# FPGA-Validation.net
KiCad netlist of a schematic drawn in EAGLE
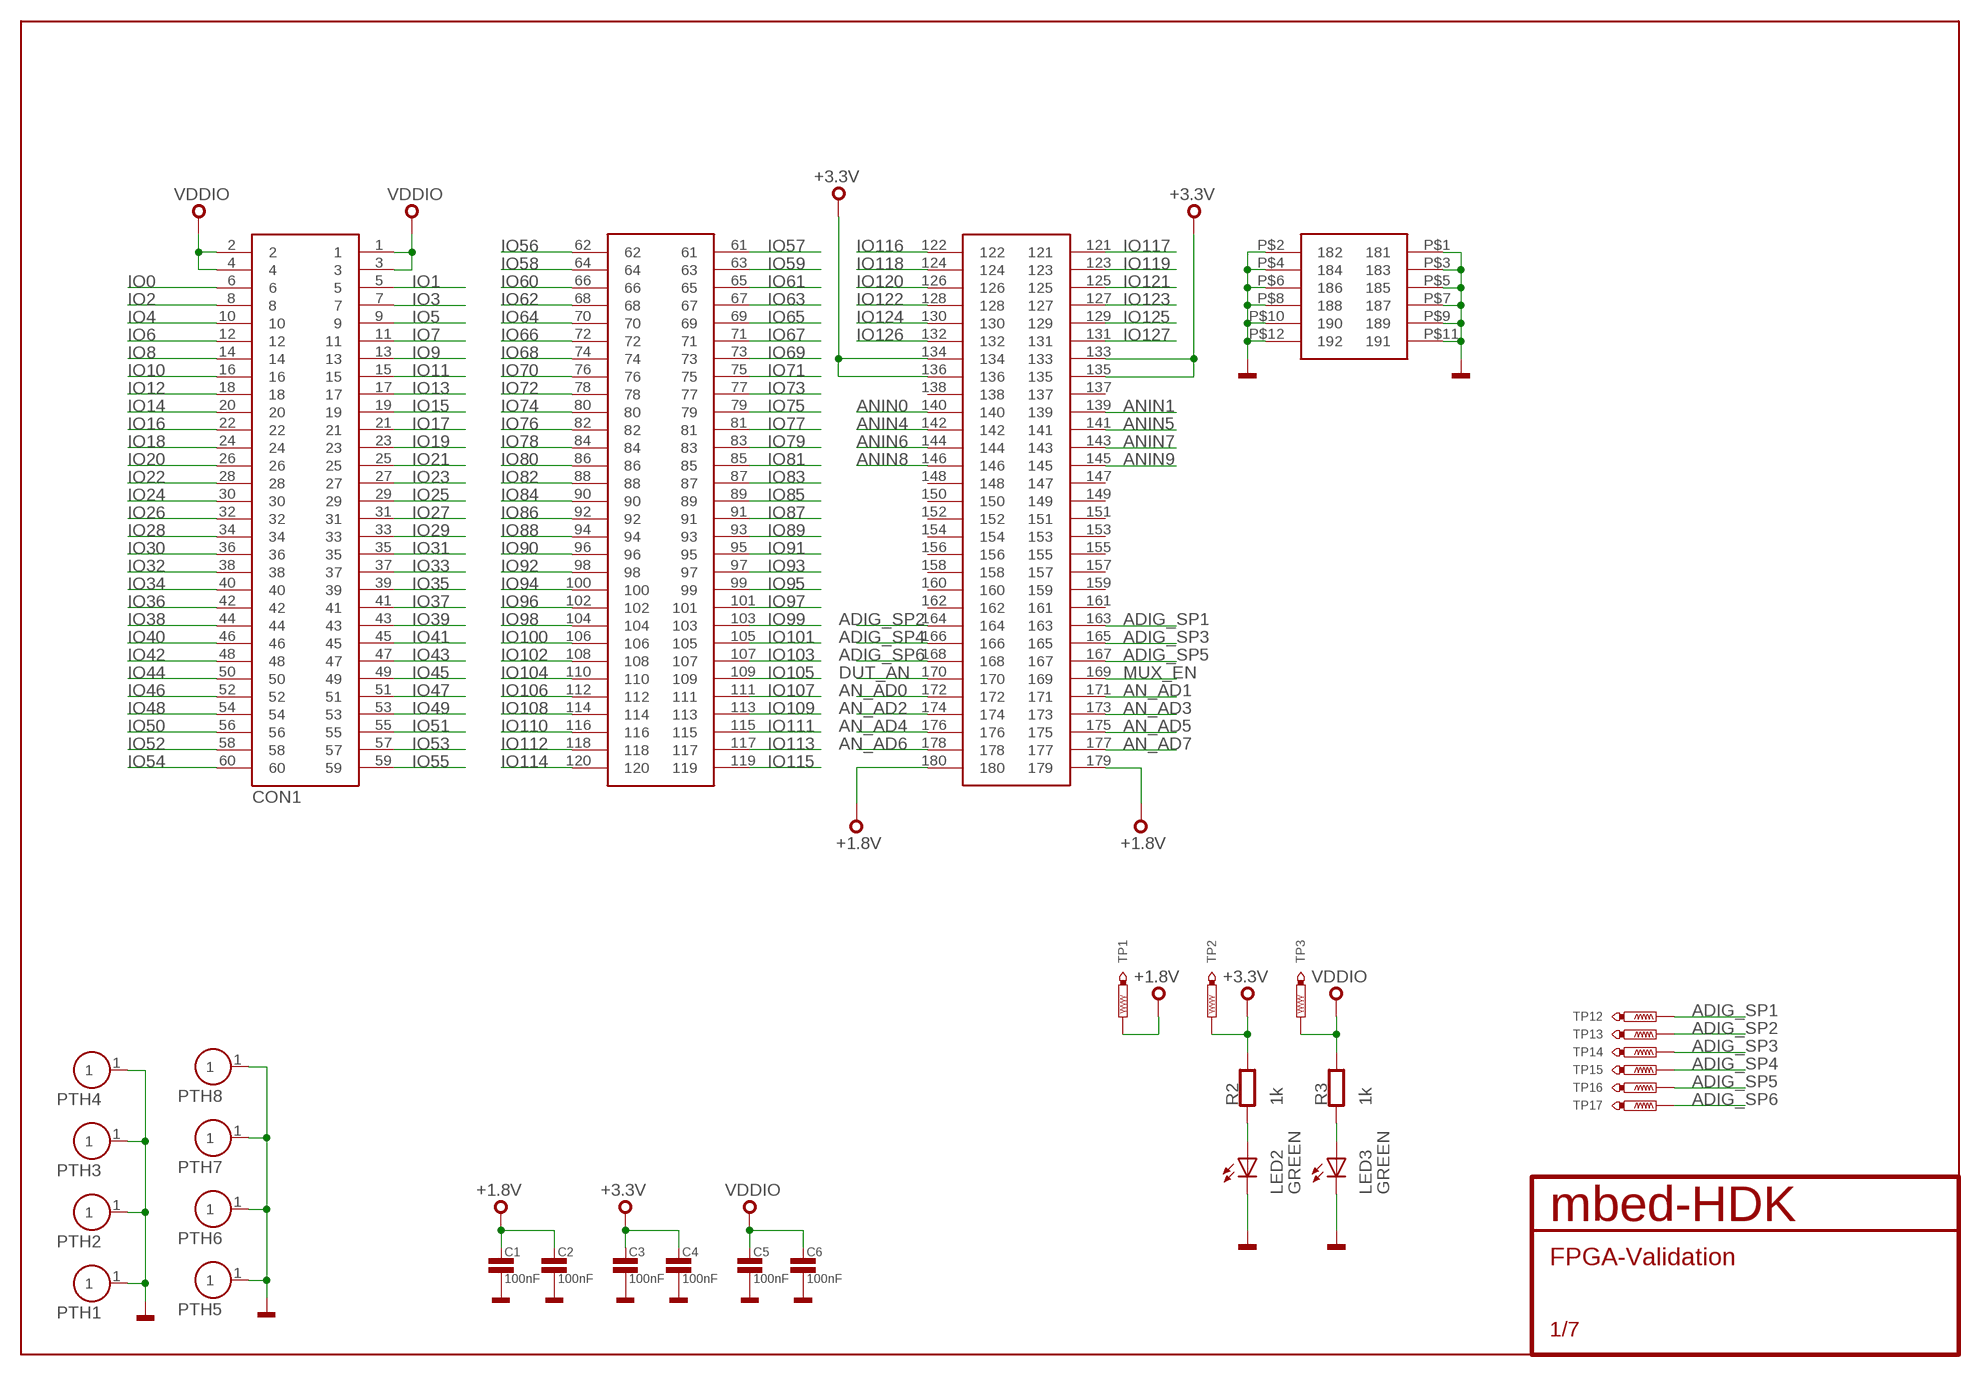
[diagram p0: schematic, sheet 1]
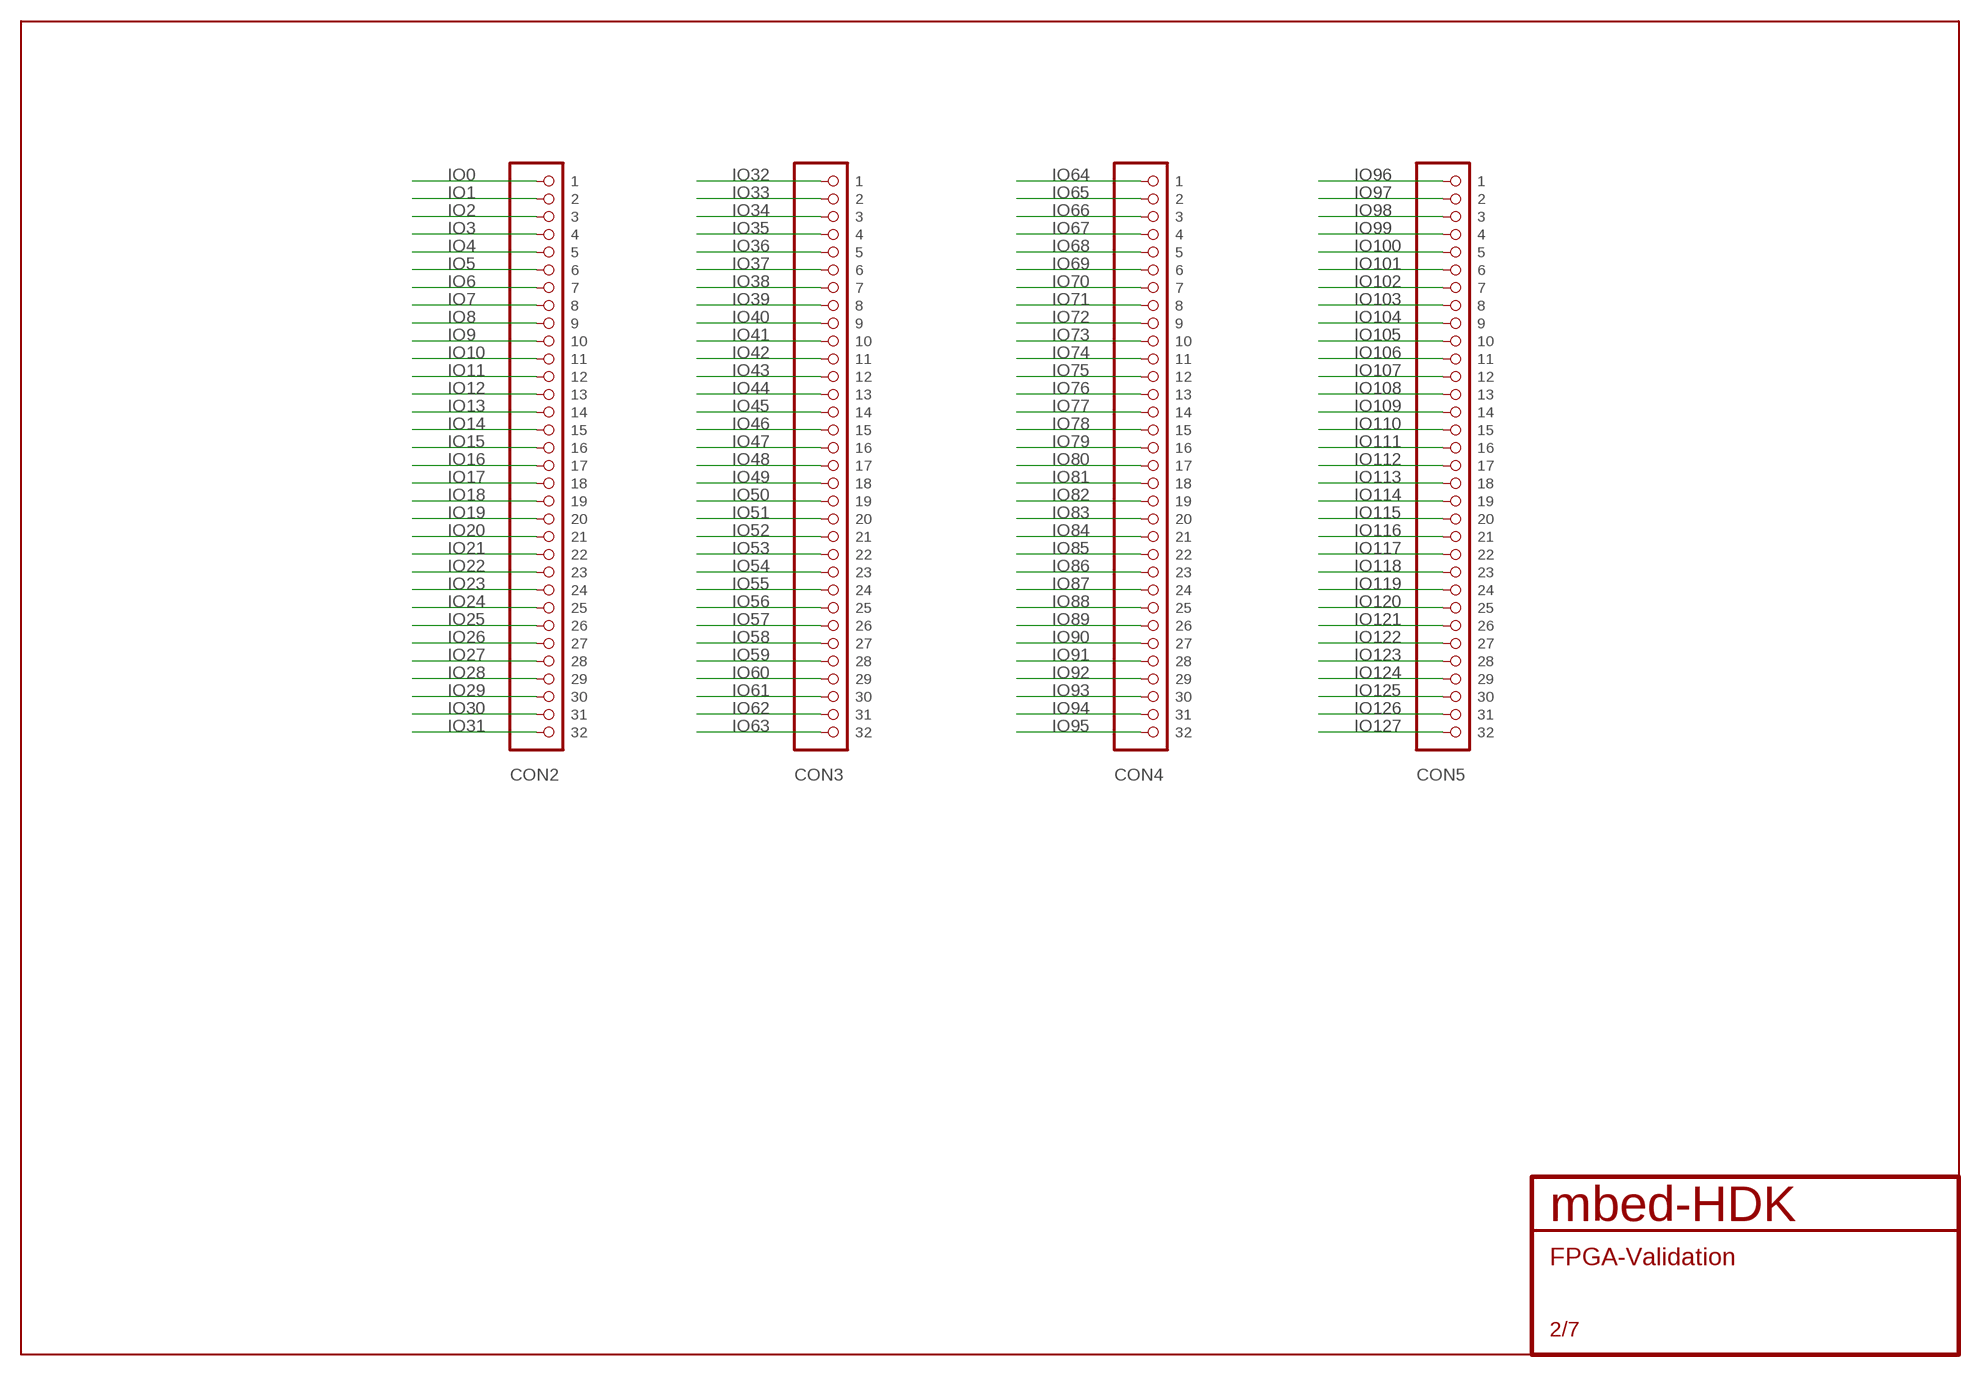
[diagram p1: schematic, sheet 2]
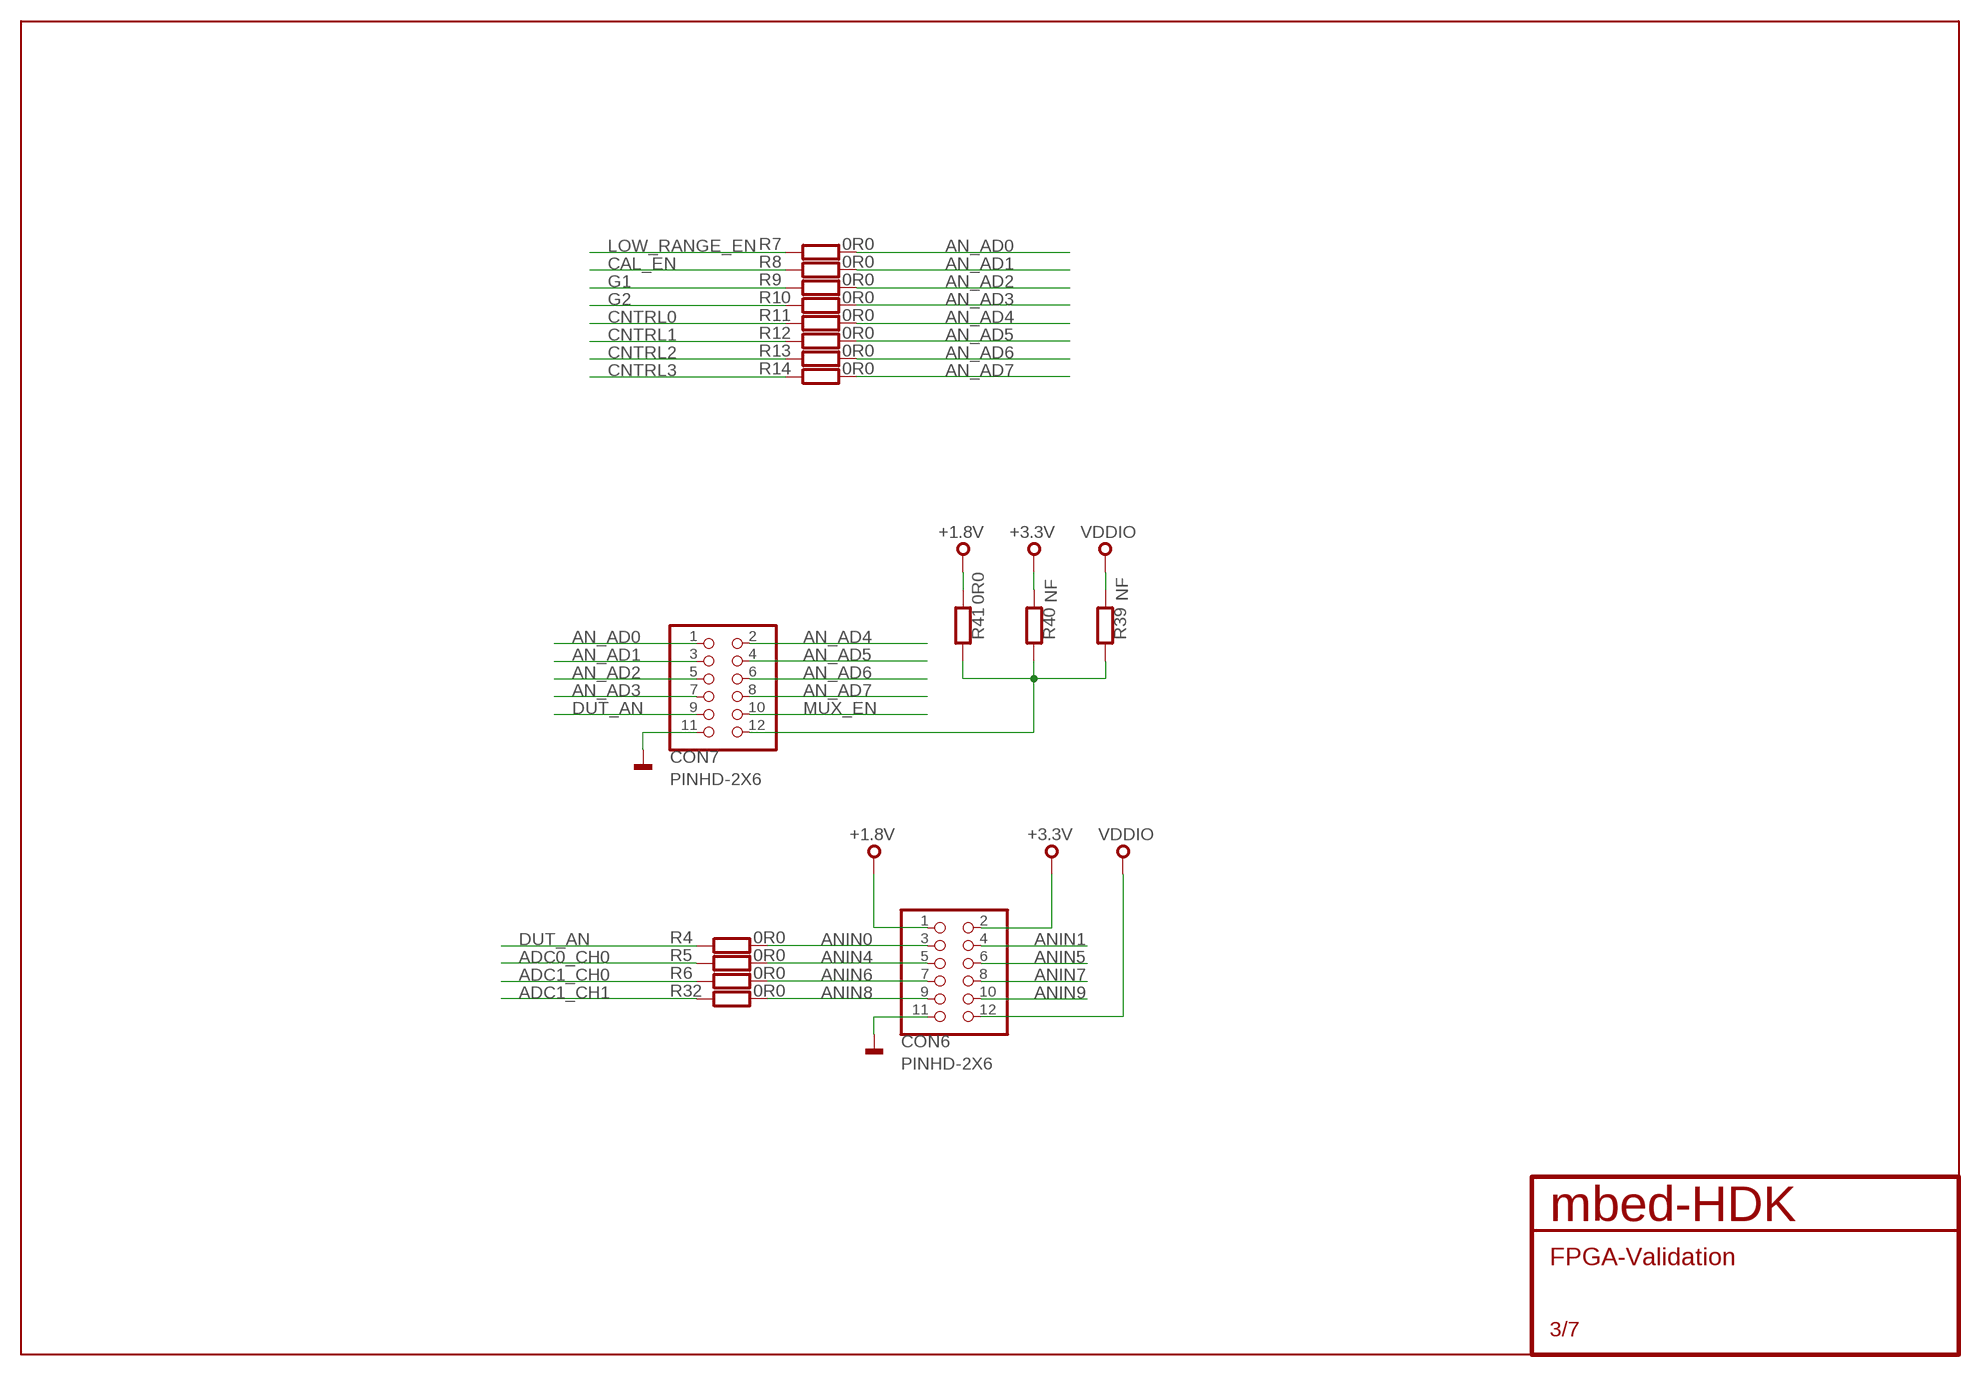
[diagram p2: schematic, sheet 3]
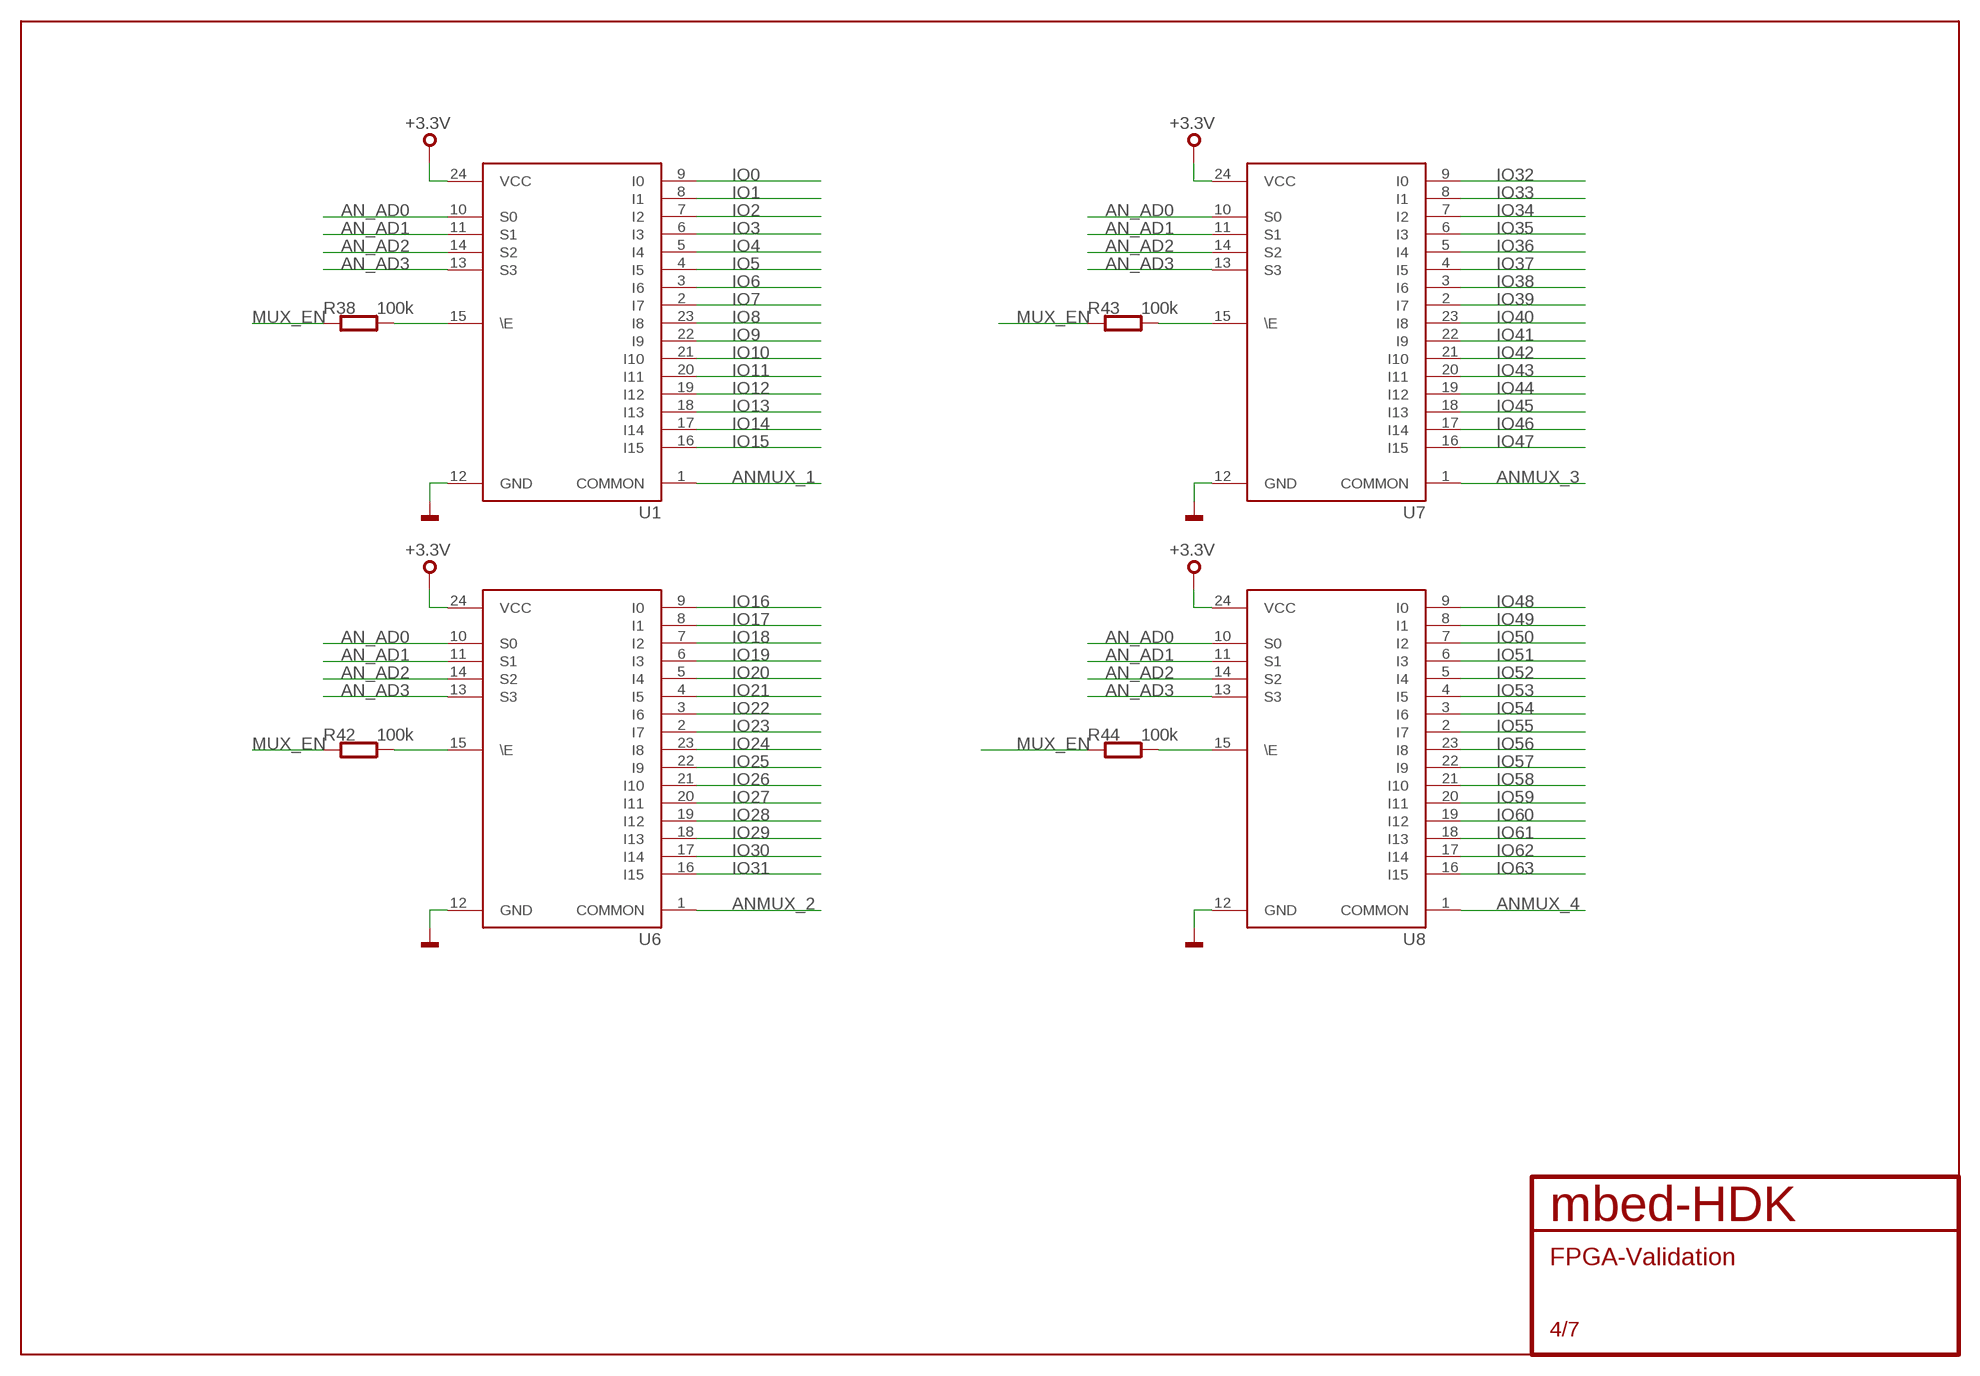
[diagram p3: schematic, sheet 4]
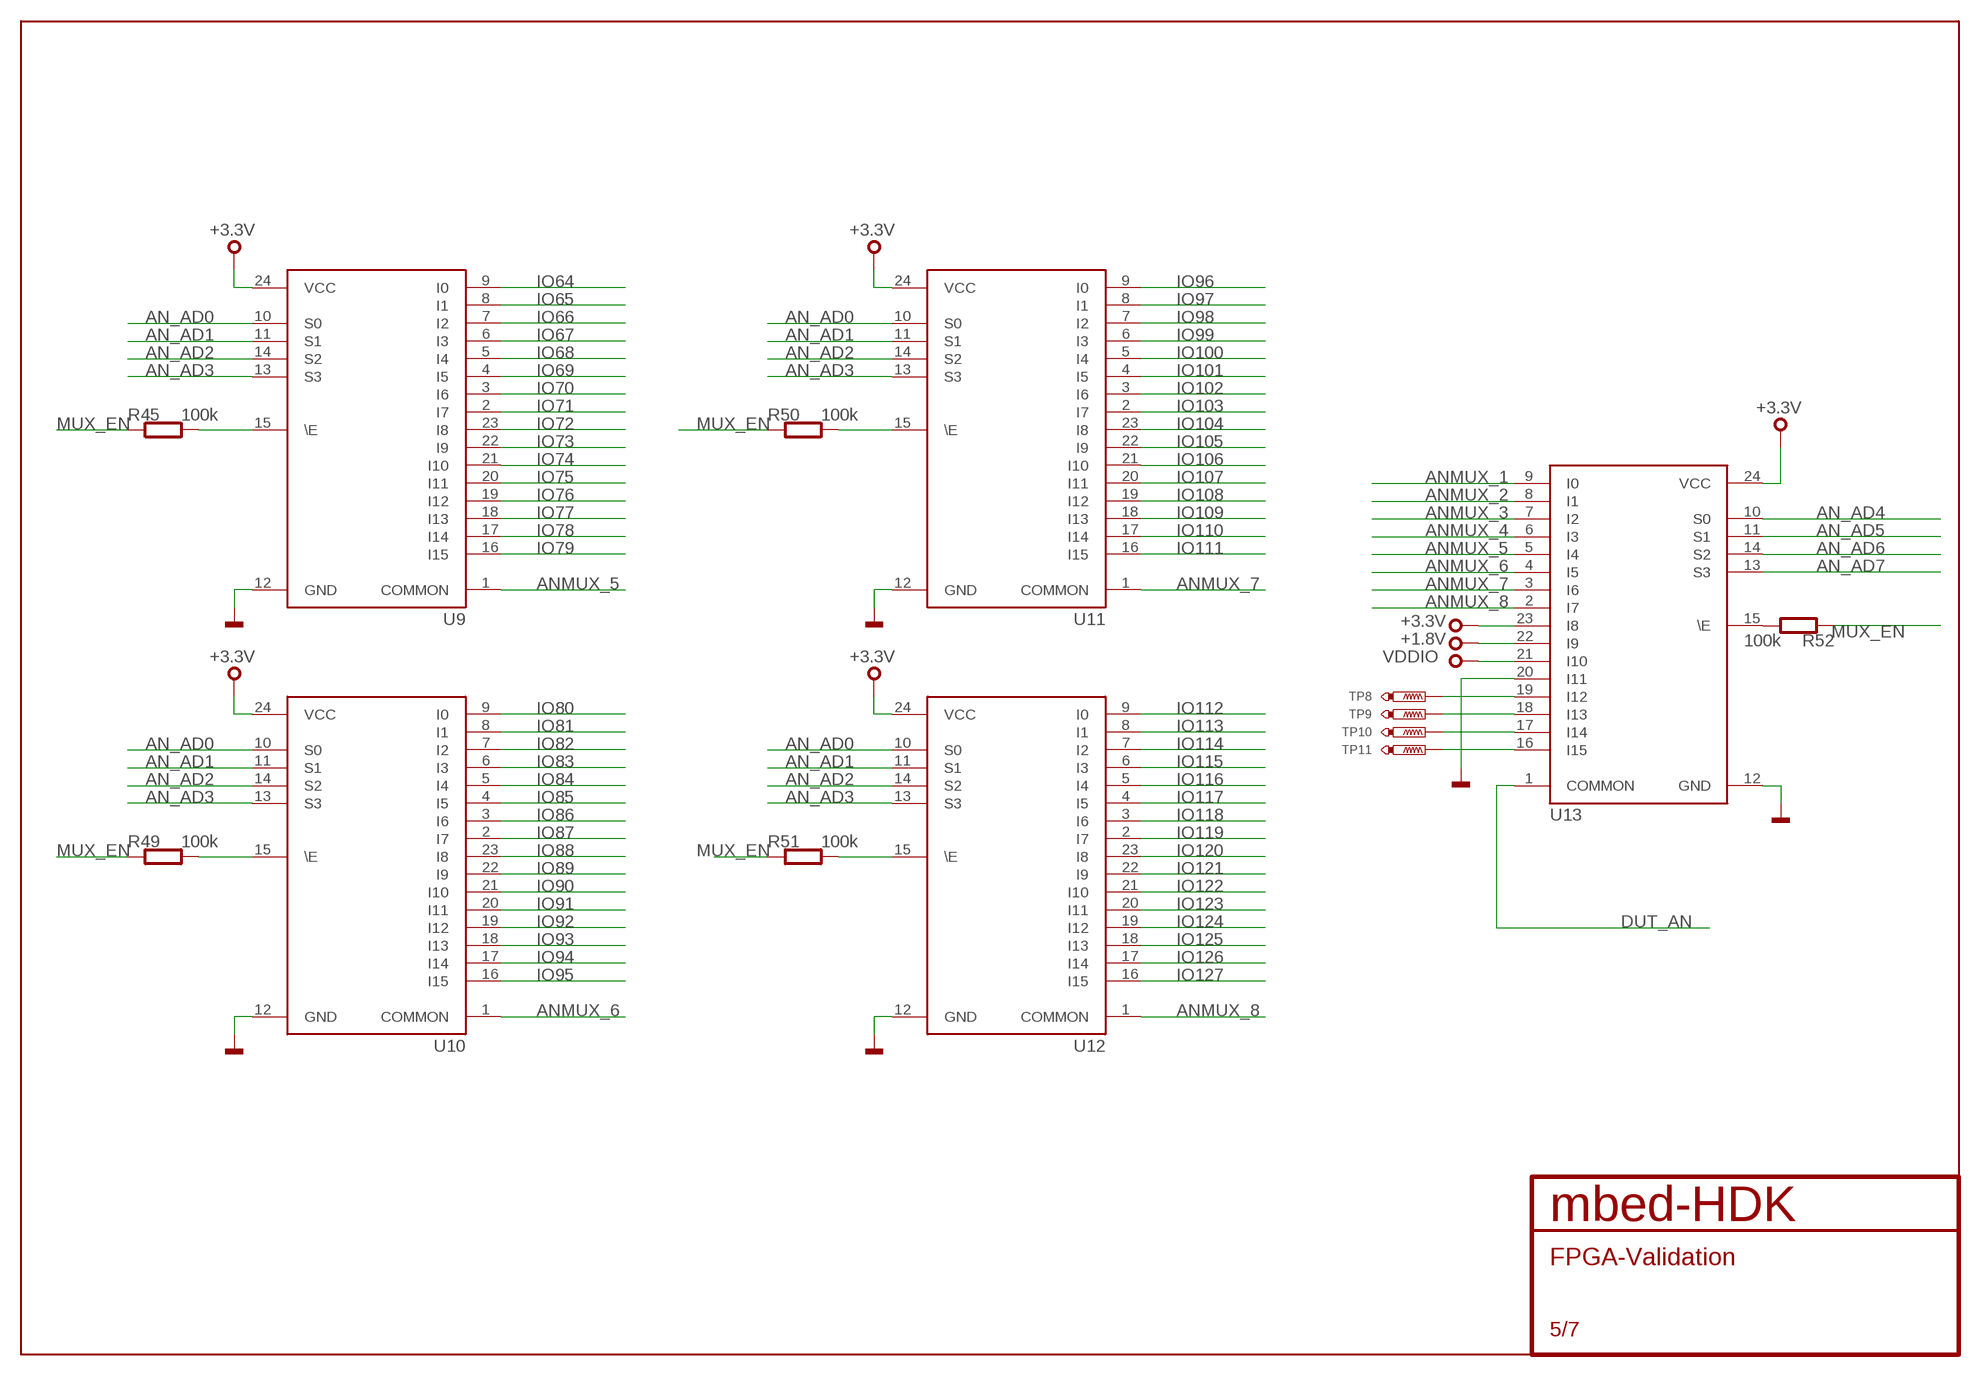
[diagram p4: schematic, sheet 5]
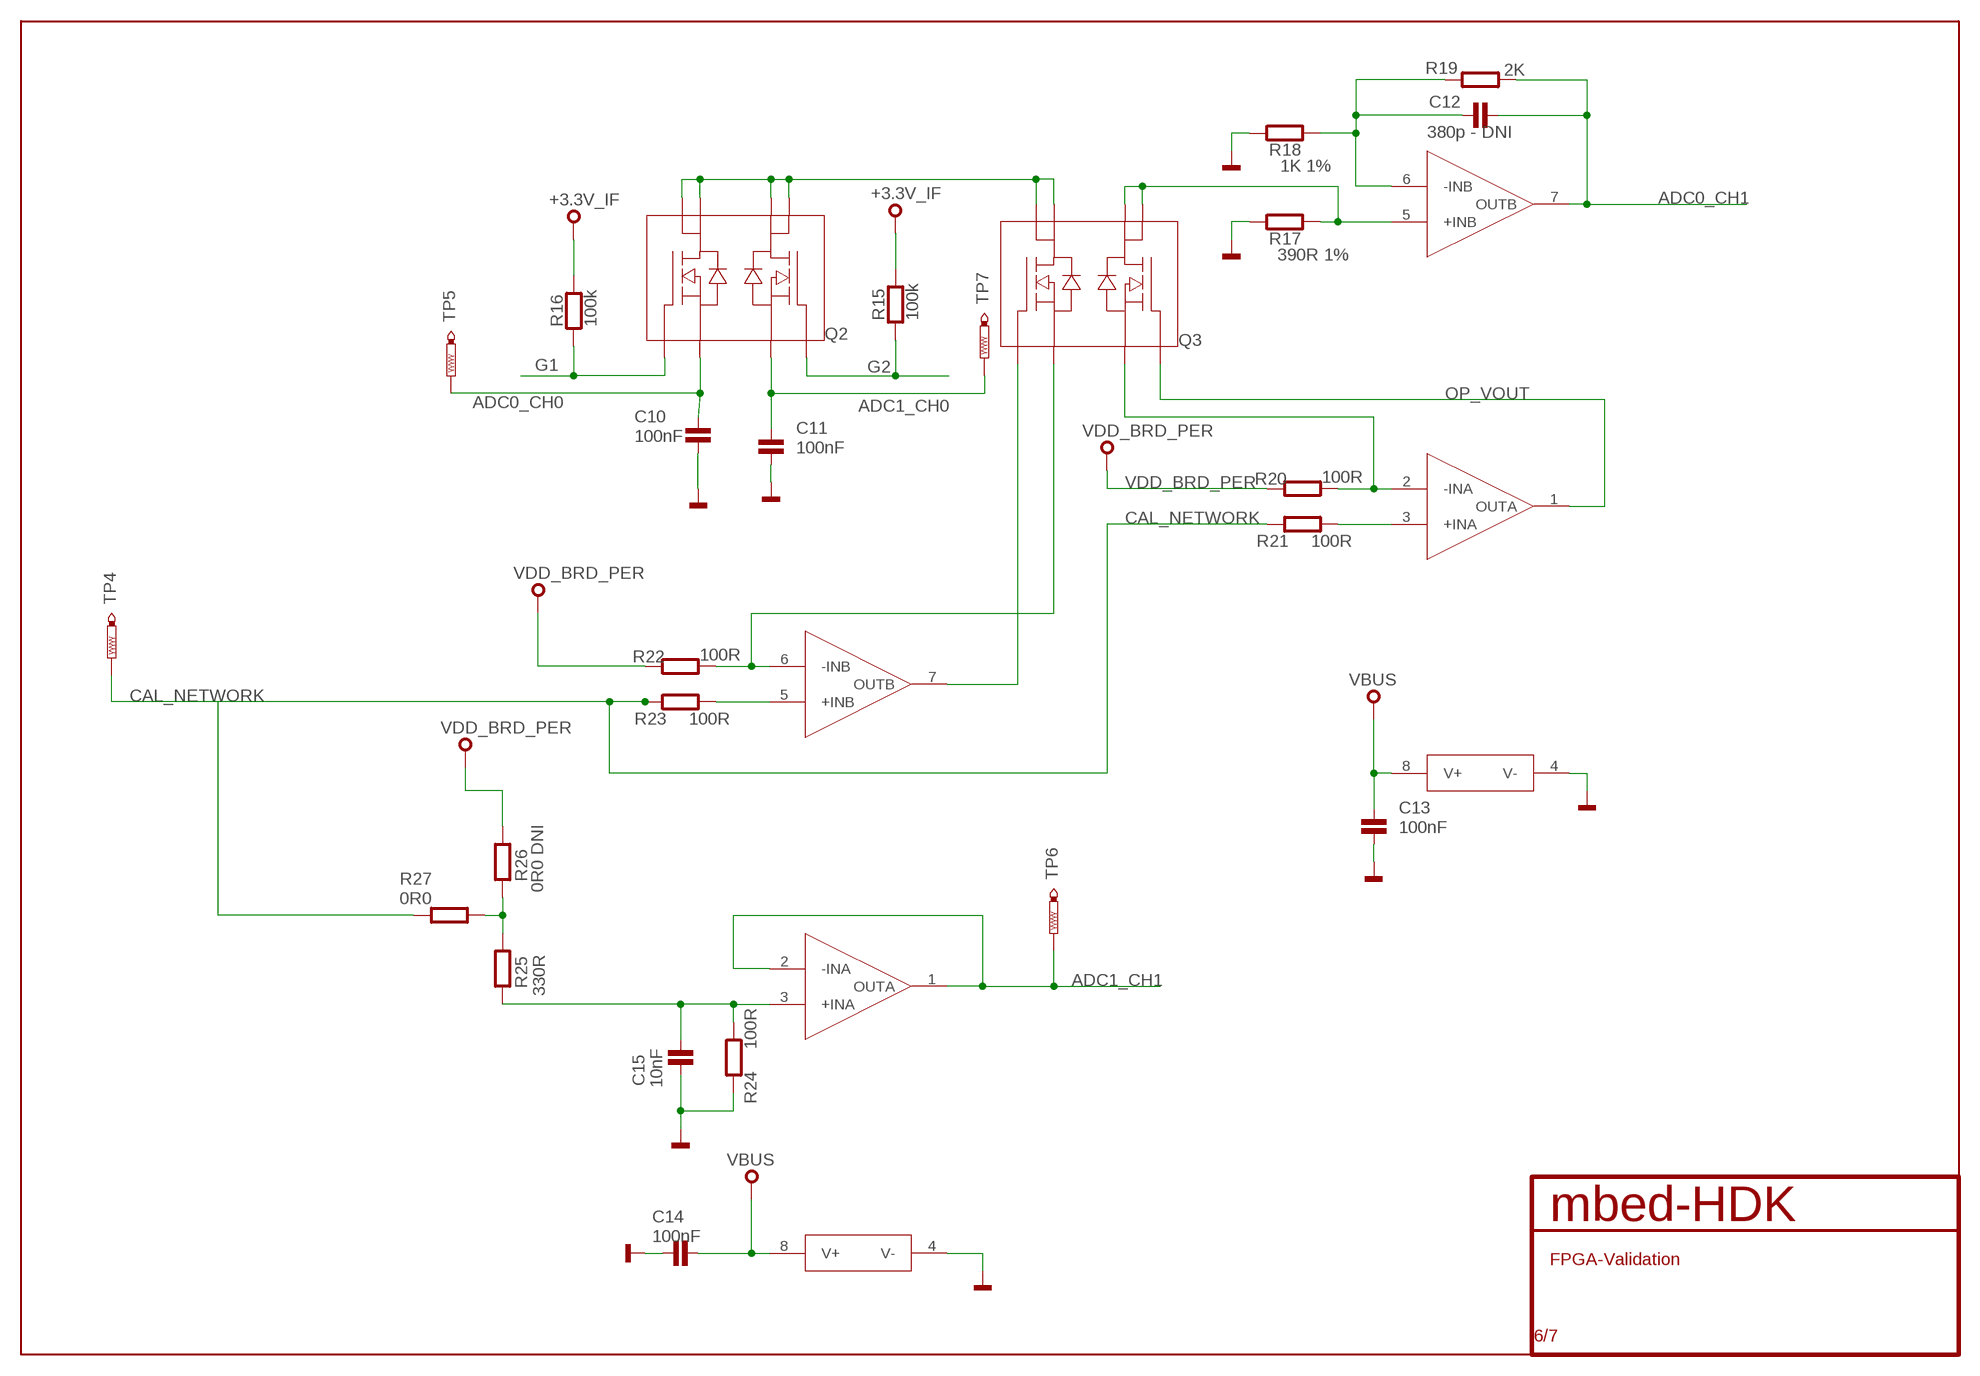
[diagram p5: schematic, sheet 6]
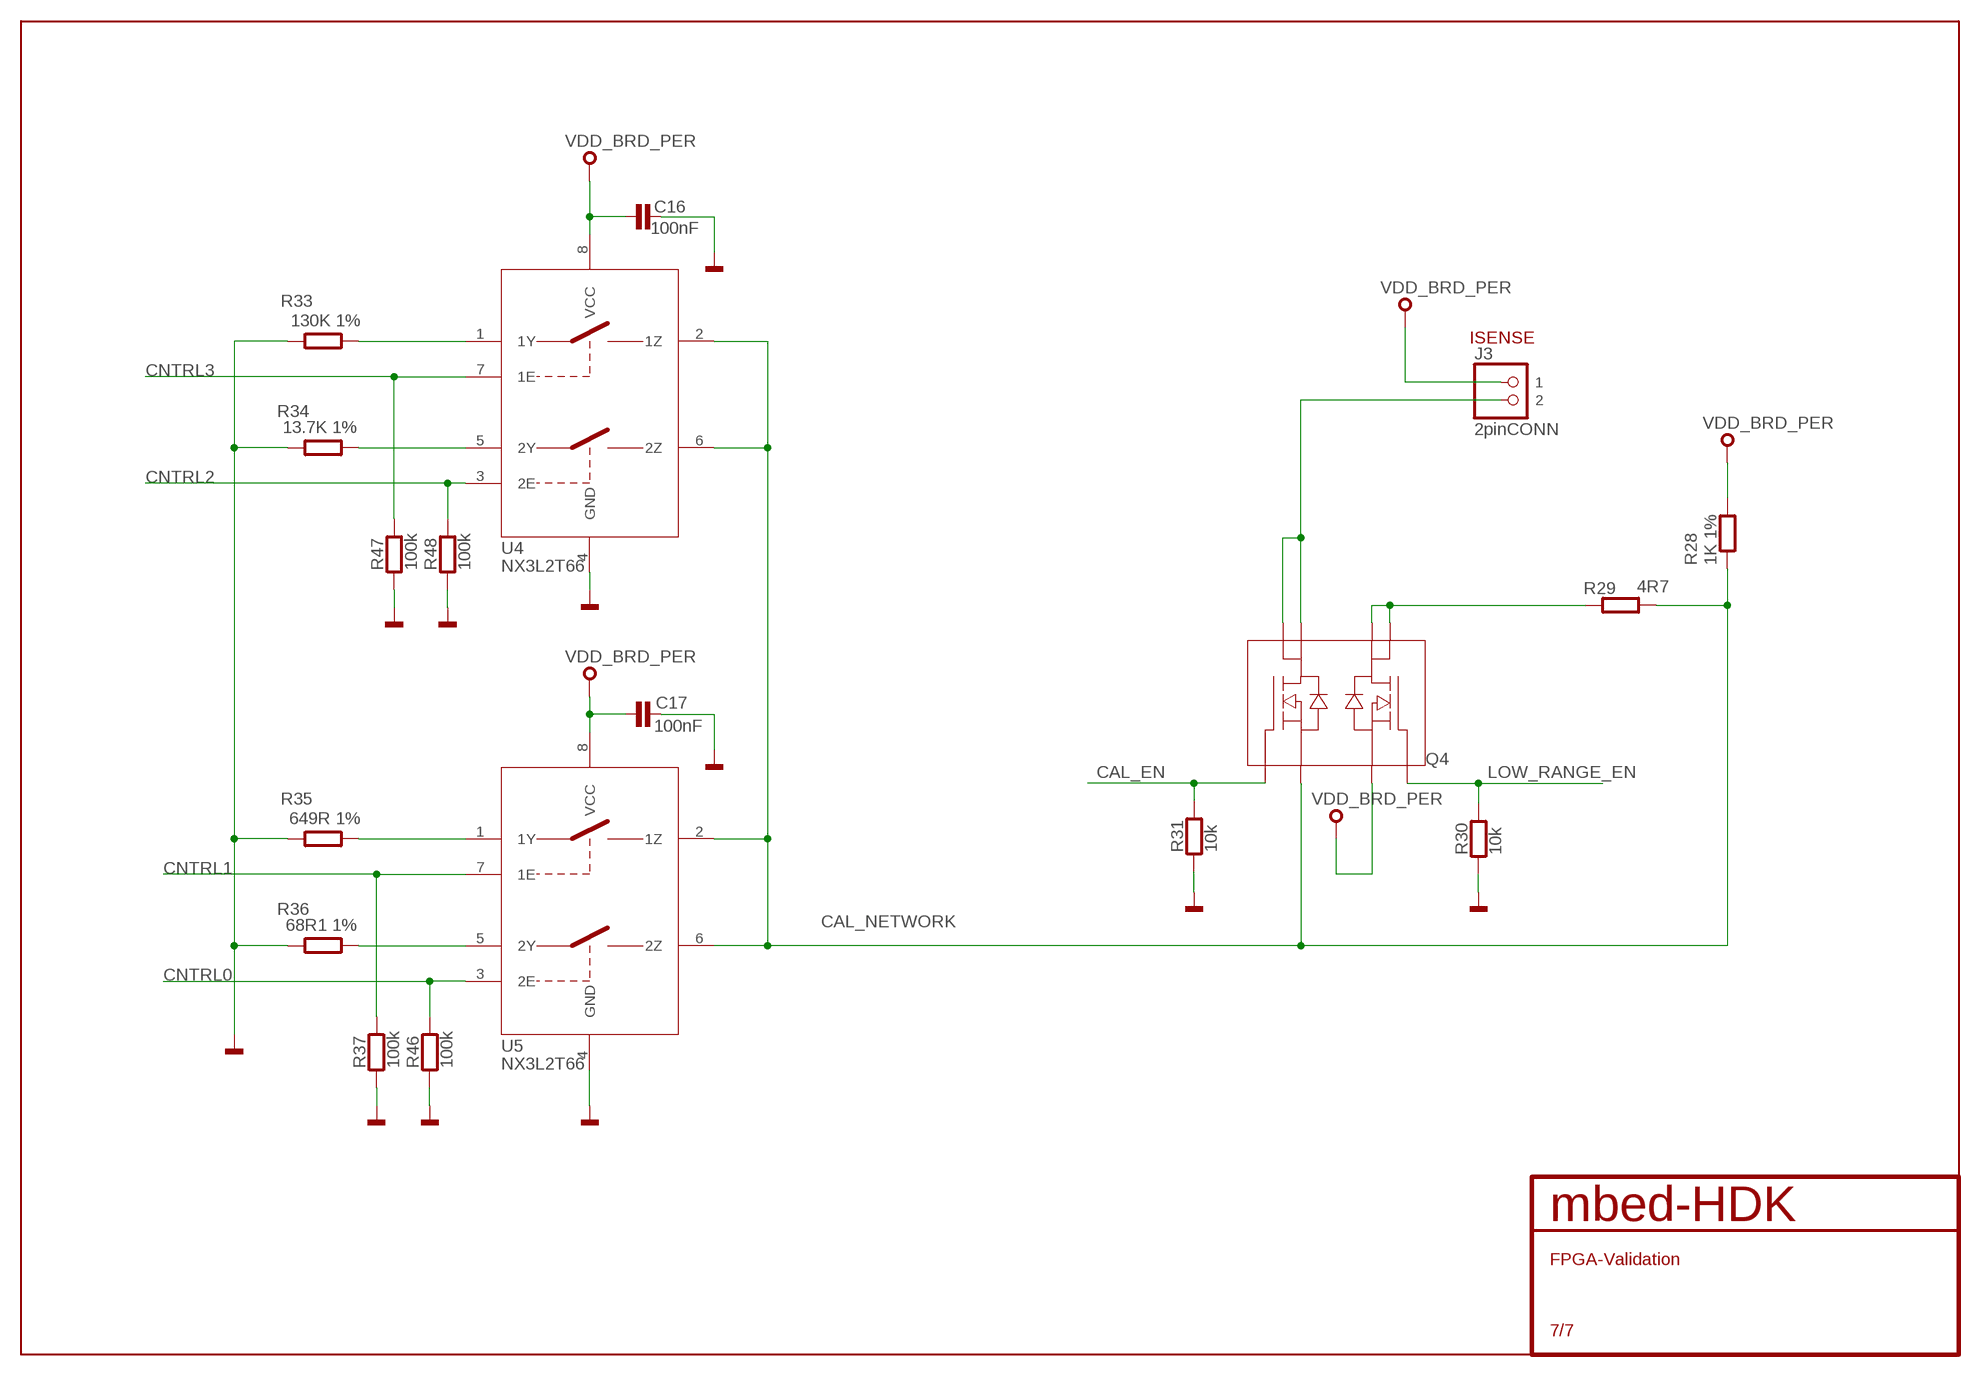
[diagram p6: schematic, sheet 7]

(export (version "E")
  (design (tool "Eeschema 10.0.6"))
  (components
    (comp (ref "C1")
      (value "100nF")
      (footprint "eagle-import:0603")
      (libsource (lib "eagle-import") (part "mbed-HDK-RLC_C0603"))
    )
    (comp (ref "C2")
      (value "100nF")
      (footprint "eagle-import:0603")
      (libsource (lib "eagle-import") (part "mbed-HDK-RLC_C0603"))
    )
    (comp (ref "C3")
      (value "100nF")
      (footprint "eagle-import:0603")
      (libsource (lib "eagle-import") (part "mbed-HDK-RLC_C0603"))
    )
    (comp (ref "C4")
      (value "100nF")
      (footprint "eagle-import:0603")
      (libsource (lib "eagle-import") (part "mbed-HDK-RLC_C0603"))
    )
    (comp (ref "C5")
      (value "100nF")
      (footprint "eagle-import:0603")
      (libsource (lib "eagle-import") (part "mbed-HDK-RLC_C0603"))
    )
    (comp (ref "C6")
      (value "100nF")
      (footprint "eagle-import:0603")
      (libsource (lib "eagle-import") (part "mbed-HDK-RLC_C0603"))
    )
    (comp (ref "CON1")
      (value "QSH-090-01-L-D-A")
      (footprint "eagle-import:QSH-090-01-L-D-A")
      (libsource (lib "eagle-import") (part "QSH-090-01-L-D-A"))
    )
    (comp (ref "LED2")
      (value "GREEN")
      (footprint "eagle-import:CHIPLED_0603")
      (libsource (lib "eagle-import") (part "LED0603"))
    )
    (comp (ref "LED3")
      (value "GREEN")
      (footprint "eagle-import:CHIPLED_0603")
      (libsource (lib "eagle-import") (part "LED0603"))
    )
    (comp (ref "PTH1")
      (value "FIXINGHOLE")
      (footprint "eagle-import:PTH-140-300")
      (libsource (lib "eagle-import") (part "FIXINGHOLE"))
    )
    (comp (ref "PTH2")
      (value "FIXINGHOLE")
      (footprint "eagle-import:PTH-140-300")
      (libsource (lib "eagle-import") (part "FIXINGHOLE"))
    )
    (comp (ref "PTH3")
      (value "FIXINGHOLE")
      (footprint "eagle-import:PTH-140-300")
      (libsource (lib "eagle-import") (part "FIXINGHOLE"))
    )
    (comp (ref "PTH4")
      (value "FIXINGHOLE")
      (footprint "eagle-import:PTH-140-300")
      (libsource (lib "eagle-import") (part "FIXINGHOLE"))
    )
    (comp (ref "PTH5")
      (value "FIXINGHOLE")
      (footprint "eagle-import:PTH-140-300")
      (libsource (lib "eagle-import") (part "FIXINGHOLE"))
    )
    (comp (ref "PTH6")
      (value "FIXINGHOLE")
      (footprint "eagle-import:PTH-140-300")
      (libsource (lib "eagle-import") (part "FIXINGHOLE"))
    )
    (comp (ref "PTH7")
      (value "FIXINGHOLE")
      (footprint "eagle-import:PTH-140-300")
      (libsource (lib "eagle-import") (part "FIXINGHOLE"))
    )
    (comp (ref "PTH8")
      (value "FIXINGHOLE")
      (footprint "eagle-import:PTH-140-300")
      (libsource (lib "eagle-import") (part "FIXINGHOLE"))
    )
    (comp (ref "R2")
      (value "1k")
      (footprint "eagle-import:0603")
      (libsource (lib "eagle-import") (part "mbed-HDK-RLC_R0603"))
    )
    (comp (ref "R3")
      (value "1k")
      (footprint "eagle-import:0603")
      (libsource (lib "eagle-import") (part "mbed-HDK-RLC_R0603"))
    )
    (comp (ref "TP1")
      (value "TEST_POINT-50R-PTH")
      (footprint "eagle-import:TP50-PTH")
      (libsource (lib "eagle-import") (part "TEST_POINT-50R-PTH"))
    )
    (comp (ref "TP2")
      (value "TEST_POINT-50R-PTH")
      (footprint "eagle-import:TP50-PTH")
      (libsource (lib "eagle-import") (part "TEST_POINT-50R-PTH"))
    )
    (comp (ref "TP3")
      (value "TEST_POINT-50R-PTH")
      (footprint "eagle-import:TP50-PTH")
      (libsource (lib "eagle-import") (part "TEST_POINT-50R-PTH"))
    )
    (comp (ref "TP12")
      (value "TEST_POINT-25R-SMD")
      (footprint "eagle-import:TP25-SMD")
      (libsource (lib "eagle-import") (part "TEST_POINT-25R-SMD"))
    )
    (comp (ref "TP13")
      (value "TEST_POINT-25R-SMD")
      (footprint "eagle-import:TP25-SMD")
      (libsource (lib "eagle-import") (part "TEST_POINT-25R-SMD"))
    )
    (comp (ref "TP14")
      (value "TEST_POINT-25R-SMD")
      (footprint "eagle-import:TP25-SMD")
      (libsource (lib "eagle-import") (part "TEST_POINT-25R-SMD"))
    )
    (comp (ref "TP15")
      (value "TEST_POINT-25R-SMD")
      (footprint "eagle-import:TP25-SMD")
      (libsource (lib "eagle-import") (part "TEST_POINT-25R-SMD"))
    )
    (comp (ref "TP16")
      (value "TEST_POINT-25R-SMD")
      (footprint "eagle-import:TP25-SMD")
      (libsource (lib "eagle-import") (part "TEST_POINT-25R-SMD"))
    )
    (comp (ref "TP17")
      (value "TEST_POINT-25R-SMD")
      (footprint "eagle-import:TP25-SMD")
      (libsource (lib "eagle-import") (part "TEST_POINT-25R-SMD"))
    )
    (comp (ref "C10")
      (value "100nF")
      (footprint "eagle-import:0603")
      (libsource (lib "eagle-import") (part "C0603"))
    )
    (comp (ref "C11")
      (value "100nF")
      (footprint "eagle-import:0603")
      (libsource (lib "eagle-import") (part "C0603"))
    )
    (comp (ref "C12")
      (value "380p - DNI")
      (footprint "eagle-import:0603")
      (libsource (lib "eagle-import") (part "C0603"))
    )
    (comp (ref "C13")
      (value "100nF")
      (footprint "eagle-import:0603")
      (libsource (lib "eagle-import") (part "C0603"))
    )
    (comp (ref "C14")
      (value "100nF")
      (footprint "eagle-import:0603")
      (libsource (lib "eagle-import") (part "C0603"))
    )
    (comp (ref "C15")
      (value "10nF")
      (footprint "eagle-import:0603")
      (libsource (lib "eagle-import") (part "C0603"))
    )
    (comp (ref "Q2")
      (value "PMDPB55XP")
      (footprint "eagle-import:SOT1118")
      (fields (field (name "MANUFACTURER") "Nexperia"))
      (libsource (lib "eagle-import") (part "PMDPB55XP"))
    )
    (comp (ref "Q3")
      (value "PMDPB55XP")
      (footprint "eagle-import:SOT1118")
      (fields (field (name "MANUFACTURER") "Nexperia"))
      (libsource (lib "eagle-import") (part "PMDPB55XP"))
    )
    (comp (ref "R15")
      (value "100k")
      (footprint "eagle-import:0603@1")
      (libsource (lib "eagle-import") (part "R0603"))
    )
    (comp (ref "R16")
      (value "100k")
      (footprint "eagle-import:0603@1")
      (libsource (lib "eagle-import") (part "R0603"))
    )
    (comp (ref "R17")
      (value "390R 1%")
      (footprint "eagle-import:0603@1")
      (libsource (lib "eagle-import") (part "R0603"))
    )
    (comp (ref "R18")
      (value "1K 1%")
      (footprint "eagle-import:0603@1")
      (libsource (lib "eagle-import") (part "R0603"))
    )
    (comp (ref "R19")
      (value "2K")
      (footprint "eagle-import:0603@1")
      (libsource (lib "eagle-import") (part "R0603"))
    )
    (comp (ref "R20")
      (value "100R")
      (footprint "eagle-import:0603@1")
      (libsource (lib "eagle-import") (part "R0603"))
    )
    (comp (ref "R21")
      (value "100R")
      (footprint "eagle-import:0603@1")
      (libsource (lib "eagle-import") (part "R0603"))
    )
    (comp (ref "R22")
      (value "100R")
      (footprint "eagle-import:0603@1")
      (libsource (lib "eagle-import") (part "R0603"))
    )
    (comp (ref "R23")
      (value "100R")
      (footprint "eagle-import:0603@1")
      (libsource (lib "eagle-import") (part "R0603"))
    )
    (comp (ref "R24")
      (value "100R")
      (footprint "eagle-import:0603@1")
      (libsource (lib "eagle-import") (part "R0603"))
    )
    (comp (ref "R25")
      (value "330R")
      (footprint "eagle-import:0603@1")
      (libsource (lib "eagle-import") (part "R0603"))
    )
    (comp (ref "R26")
      (value "0R0 DNI")
      (footprint "eagle-import:0603@1")
      (libsource (lib "eagle-import") (part "R0603"))
    )
    (comp (ref "R27")
      (value "0R0")
      (footprint "eagle-import:0603@1")
      (libsource (lib "eagle-import") (part "R0603"))
    )
    (comp (ref "TP4")
      (value "TEST-POINT-50R-PTH")
      (footprint "eagle-import:TP50-PTH")
      (libsource (lib "eagle-import") (part "TEST-POINT-50R-PTH"))
    )
    (comp (ref "TP5")
      (value "TEST-POINT-50R-PTH")
      (footprint "eagle-import:TP50-PTH")
      (libsource (lib "eagle-import") (part "TEST-POINT-50R-PTH"))
    )
    (comp (ref "TP6")
      (value "TEST-POINT-50R-PTH")
      (footprint "eagle-import:TP50-PTH")
      (libsource (lib "eagle-import") (part "TEST-POINT-50R-PTH"))
    )
    (comp (ref "TP7")
      (value "TEST-POINT-50R-PTH")
      (footprint "eagle-import:TP50-PTH")
      (libsource (lib "eagle-import") (part "TEST-POINT-50R-PTH"))
    )
    (comp (ref "U2")
      (value "LTC2051IMS8")
      (footprint "eagle-import:MSOP8")
      (fields (field (name "MANUFACTURER") "Linear Technology"))
      (libsource (lib "eagle-import") (part "LTC2051IMS8"))
    )
    (comp (ref "U3")
      (value "LTC2051IMS8")
      (footprint "eagle-import:MSOP8")
      (fields (field (name "MANUFACTURER") "Linear Technology"))
      (libsource (lib "eagle-import") (part "LTC2051IMS8"))
    )
    (comp (ref "R38")
      (value "100k")
      (footprint "eagle-import:0603")
      (libsource (lib "eagle-import") (part "mbed-HDK-RLC_R0603"))
    )
    (comp (ref "R42")
      (value "100k")
      (footprint "eagle-import:0603")
      (libsource (lib "eagle-import") (part "mbed-HDK-RLC_R0603"))
    )
    (comp (ref "R43")
      (value "100k")
      (footprint "eagle-import:0603")
      (libsource (lib "eagle-import") (part "mbed-HDK-RLC_R0603"))
    )
    (comp (ref "R44")
      (value "100k")
      (footprint "eagle-import:0603")
      (libsource (lib "eagle-import") (part "mbed-HDK-RLC_R0603"))
    )
    (comp (ref "U1")
      (value "CD74HCT4067")
      (footprint "eagle-import:SO24")
      (libsource (lib "eagle-import") (part "CD74HCT4067"))
    )
    (comp (ref "U6")
      (value "CD74HCT4067")
      (footprint "eagle-import:SO24")
      (libsource (lib "eagle-import") (part "CD74HCT4067"))
    )
    (comp (ref "U7")
      (value "CD74HCT4067")
      (footprint "eagle-import:SO24")
      (libsource (lib "eagle-import") (part "CD74HCT4067"))
    )
    (comp (ref "U8")
      (value "CD74HCT4067")
      (footprint "eagle-import:SO24")
      (libsource (lib "eagle-import") (part "CD74HCT4067"))
    )
    (comp (ref "CON2")
      (value "PINHD-1X32")
      (footprint "eagle-import:1X32")
      (libsource (lib "eagle-import") (part "PINHD-1X32"))
    )
    (comp (ref "CON3")
      (value "PINHD-1X32")
      (footprint "eagle-import:1X32")
      (libsource (lib "eagle-import") (part "PINHD-1X32"))
    )
    (comp (ref "CON4")
      (value "PINHD-1X32")
      (footprint "eagle-import:1X32")
      (libsource (lib "eagle-import") (part "PINHD-1X32"))
    )
    (comp (ref "CON5")
      (value "PINHD-1X32")
      (footprint "eagle-import:1X32")
      (libsource (lib "eagle-import") (part "PINHD-1X32"))
    )
    (comp (ref "R45")
      (value "100k")
      (footprint "eagle-import:0603")
      (libsource (lib "eagle-import") (part "mbed-HDK-RLC_R0603"))
    )
    (comp (ref "R49")
      (value "100k")
      (footprint "eagle-import:0603")
      (libsource (lib "eagle-import") (part "mbed-HDK-RLC_R0603"))
    )
    (comp (ref "R50")
      (value "100k")
      (footprint "eagle-import:0603")
      (libsource (lib "eagle-import") (part "mbed-HDK-RLC_R0603"))
    )
    (comp (ref "R51")
      (value "100k")
      (footprint "eagle-import:0603")
      (libsource (lib "eagle-import") (part "mbed-HDK-RLC_R0603"))
    )
    (comp (ref "R52")
      (value "100k")
      (footprint "eagle-import:0603")
      (libsource (lib "eagle-import") (part "mbed-HDK-RLC_R0603"))
    )
    (comp (ref "TP8")
      (value "TEST_POINT-50R-PTH")
      (footprint "eagle-import:TP50-PTH")
      (libsource (lib "eagle-import") (part "TEST_POINT-50R-PTH"))
    )
    (comp (ref "TP9")
      (value "TEST_POINT-50R-PTH")
      (footprint "eagle-import:TP50-PTH")
      (libsource (lib "eagle-import") (part "TEST_POINT-50R-PTH"))
    )
    (comp (ref "TP10")
      (value "TEST_POINT-50R-PTH")
      (footprint "eagle-import:TP50-PTH")
      (libsource (lib "eagle-import") (part "TEST_POINT-50R-PTH"))
    )
    (comp (ref "TP11")
      (value "TEST_POINT-50R-PTH")
      (footprint "eagle-import:TP50-PTH")
      (libsource (lib "eagle-import") (part "TEST_POINT-50R-PTH"))
    )
    (comp (ref "U9")
      (value "CD74HCT4067")
      (footprint "eagle-import:SO24")
      (libsource (lib "eagle-import") (part "CD74HCT4067"))
    )
    (comp (ref "U10")
      (value "CD74HCT4067")
      (footprint "eagle-import:SO24")
      (libsource (lib "eagle-import") (part "CD74HCT4067"))
    )
    (comp (ref "U11")
      (value "CD74HCT4067")
      (footprint "eagle-import:SO24")
      (libsource (lib "eagle-import") (part "CD74HCT4067"))
    )
    (comp (ref "U12")
      (value "CD74HCT4067")
      (footprint "eagle-import:SO24")
      (libsource (lib "eagle-import") (part "CD74HCT4067"))
    )
    (comp (ref "U13")
      (value "CD74HCT4067")
      (footprint "eagle-import:SO24")
      (libsource (lib "eagle-import") (part "CD74HCT4067"))
    )
    (comp (ref "CON6")
      (value "PINHD-2X6")
      (footprint "eagle-import:2X06")
      (libsource (lib "eagle-import") (part "PINHD-2X6"))
    )
    (comp (ref "CON7")
      (value "PINHD-2X6")
      (footprint "eagle-import:2X06")
      (libsource (lib "eagle-import") (part "PINHD-2X6"))
    )
    (comp (ref "R4")
      (value "0R0")
      (footprint "eagle-import:0603")
      (libsource (lib "eagle-import") (part "mbed-HDK-RLC_R0603"))
    )
    (comp (ref "R5")
      (value "0R0")
      (footprint "eagle-import:0603")
      (libsource (lib "eagle-import") (part "mbed-HDK-RLC_R0603"))
    )
    (comp (ref "R6")
      (value "0R0")
      (footprint "eagle-import:0603")
      (libsource (lib "eagle-import") (part "mbed-HDK-RLC_R0603"))
    )
    (comp (ref "R7")
      (value "0R0")
      (footprint "eagle-import:0603")
      (libsource (lib "eagle-import") (part "mbed-HDK-RLC_R0603"))
    )
    (comp (ref "R8")
      (value "0R0")
      (footprint "eagle-import:0603")
      (libsource (lib "eagle-import") (part "mbed-HDK-RLC_R0603"))
    )
    (comp (ref "R9")
      (value "0R0")
      (footprint "eagle-import:0603")
      (libsource (lib "eagle-import") (part "mbed-HDK-RLC_R0603"))
    )
    (comp (ref "R10")
      (value "0R0")
      (footprint "eagle-import:0603")
      (libsource (lib "eagle-import") (part "mbed-HDK-RLC_R0603"))
    )
    (comp (ref "R11")
      (value "0R0")
      (footprint "eagle-import:0603")
      (libsource (lib "eagle-import") (part "mbed-HDK-RLC_R0603"))
    )
    (comp (ref "R12")
      (value "0R0")
      (footprint "eagle-import:0603")
      (libsource (lib "eagle-import") (part "mbed-HDK-RLC_R0603"))
    )
    (comp (ref "R13")
      (value "0R0")
      (footprint "eagle-import:0603")
      (libsource (lib "eagle-import") (part "mbed-HDK-RLC_R0603"))
    )
    (comp (ref "R14")
      (value "0R0")
      (footprint "eagle-import:0603")
      (libsource (lib "eagle-import") (part "mbed-HDK-RLC_R0603"))
    )
    (comp (ref "R32")
      (value "0R0")
      (footprint "eagle-import:0603")
      (libsource (lib "eagle-import") (part "mbed-HDK-RLC_R0603"))
    )
    (comp (ref "R39")
      (value "NF")
      (footprint "eagle-import:0603")
      (libsource (lib "eagle-import") (part "mbed-HDK-RLC_R0603"))
    )
    (comp (ref "R40")
      (value "NF")
      (footprint "eagle-import:0603")
      (libsource (lib "eagle-import") (part "mbed-HDK-RLC_R0603"))
    )
    (comp (ref "R41")
      (value "0R0")
      (footprint "eagle-import:0603")
      (libsource (lib "eagle-import") (part "mbed-HDK-RLC_R0603"))
    )
    (comp (ref "C16")
      (value "100nF")
      (footprint "eagle-import:0603")
      (libsource (lib "eagle-import") (part "C0603"))
    )
    (comp (ref "C17")
      (value "100nF")
      (footprint "eagle-import:0603")
      (libsource (lib "eagle-import") (part "C0603"))
    )
    (comp (ref "J3")
      (value "2pinCONN")
      (footprint "eagle-import:1X02")
      (fields (field (name "MF") "Wurth"))
      (libsource (lib "eagle-import") (part "PINHD-1X2"))
    )
    (comp (ref "Q4")
      (value "PMDPB55XP")
      (footprint "eagle-import:SOT1118")
      (fields (field (name "MANUFACTURER") "Nexperia"))
      (libsource (lib "eagle-import") (part "PMDPB55XP"))
    )
    (comp (ref "R28")
      (value "1K 1%")
      (footprint "eagle-import:0603@1")
      (libsource (lib "eagle-import") (part "R0603"))
    )
    (comp (ref "R29")
      (value "4R7")
      (footprint "eagle-import:0603@1")
      (libsource (lib "eagle-import") (part "R0603"))
    )
    (comp (ref "R30")
      (value "10k")
      (footprint "eagle-import:0603@1")
      (libsource (lib "eagle-import") (part "R0603"))
    )
    (comp (ref "R31")
      (value "10k")
      (footprint "eagle-import:0603@1")
      (libsource (lib "eagle-import") (part "R0603"))
    )
    (comp (ref "R33")
      (value "130K 1%")
      (footprint "eagle-import:0603@1")
      (libsource (lib "eagle-import") (part "R0603"))
    )
    (comp (ref "R34")
      (value "13.7K 1%")
      (footprint "eagle-import:0603@1")
      (libsource (lib "eagle-import") (part "R0603"))
    )
    (comp (ref "R35")
      (value "649R 1%")
      (footprint "eagle-import:0603@1")
      (libsource (lib "eagle-import") (part "R0603"))
    )
    (comp (ref "R36")
      (value "68R1 1%")
      (footprint "eagle-import:0603@1")
      (libsource (lib "eagle-import") (part "R0603"))
    )
    (comp (ref "R37")
      (value "100k")
      (footprint "eagle-import:0603@1")
      (libsource (lib "eagle-import") (part "R0603"))
    )
    (comp (ref "R46")
      (value "100k")
      (footprint "eagle-import:0603@1")
      (libsource (lib "eagle-import") (part "R0603"))
    )
    (comp (ref "R47")
      (value "100k")
      (footprint "eagle-import:0603@1")
      (libsource (lib "eagle-import") (part "R0603"))
    )
    (comp (ref "R48")
      (value "100k")
      (footprint "eagle-import:0603@1")
      (libsource (lib "eagle-import") (part "R0603"))
    )
    (comp (ref "U4")
      (value "NX3L2T66")
      (footprint "eagle-import:XSON8")
      (fields (field (name "MANUFACTURER") "NXP USA Inc."))
      (libsource (lib "eagle-import") (part "NX3L2T66"))
    )
    (comp (ref "U5")
      (value "NX3L2T66")
      (footprint "eagle-import:XSON8")
      (fields (field (name "MANUFACTURER") "NXP USA Inc."))
      (libsource (lib "eagle-import") (part "NX3L2T66"))
    )
  )
  (nets
    (net (code "1") (name "+1.8V") (class "Default")
      (node (ref "C1") (pin "1") (pinfunction "P$1_1") (pintype "passive"))
      (node (ref "C2") (pin "1") (pinfunction "P$1_1") (pintype "passive"))
      (node (ref "CON1") (pin "179") (pinfunction "179_179") (pintype "bidirectional"))
      (node (ref "CON1") (pin "180") (pinfunction "180_180") (pintype "bidirectional"))
      (node (ref "CON6") (pin "1") (pinfunction "1_1") (pintype "passive"))
      (node (ref "R41") (pin "1") (pinfunction "P$1_1") (pintype "passive"))
      (node (ref "TP1") (pin "TP") (pinfunction "TP_TP") (pintype "input"))
      (node (ref "U13") (pin "22") (pinfunction "I9_22") (pintype "bidirectional"))
    )
    (net (code "2") (name "+3.3V") (class "Default")
      (node (ref "C3") (pin "1") (pinfunction "P$1_1") (pintype "passive"))
      (node (ref "C4") (pin "1") (pinfunction "P$1_1") (pintype "passive"))
      (node (ref "CON1") (pin "133") (pinfunction "133_133") (pintype "bidirectional"))
      (node (ref "CON1") (pin "134") (pinfunction "134_134") (pintype "bidirectional"))
      (node (ref "CON1") (pin "135") (pinfunction "135_135") (pintype "bidirectional"))
      (node (ref "CON1") (pin "136") (pinfunction "136_136") (pintype "bidirectional"))
      (node (ref "CON6") (pin "2") (pinfunction "2_2") (pintype "passive"))
      (node (ref "R2") (pin "2") (pinfunction "P$2_2") (pintype "passive"))
      (node (ref "R40") (pin "1") (pinfunction "P$1_1") (pintype "passive"))
      (node (ref "TP2") (pin "TP") (pinfunction "TP_TP") (pintype "input"))
      (node (ref "U1") (pin "24") (pinfunction "VCC_24") (pintype "bidirectional"))
      (node (ref "U10") (pin "24") (pinfunction "VCC_24") (pintype "bidirectional"))
      (node (ref "U11") (pin "24") (pinfunction "VCC_24") (pintype "bidirectional"))
      (node (ref "U12") (pin "24") (pinfunction "VCC_24") (pintype "bidirectional"))
      (node (ref "U13") (pin "23") (pinfunction "I8_23") (pintype "bidirectional"))
      (node (ref "U13") (pin "24") (pinfunction "VCC_24") (pintype "bidirectional"))
      (node (ref "U6") (pin "24") (pinfunction "VCC_24") (pintype "bidirectional"))
      (node (ref "U7") (pin "24") (pinfunction "VCC_24") (pintype "bidirectional"))
      (node (ref "U8") (pin "24") (pinfunction "VCC_24") (pintype "bidirectional"))
      (node (ref "U9") (pin "24") (pinfunction "VCC_24") (pintype "bidirectional"))
    )
    (net (code "3") (name "+3.3V_IF") (class "Default")
      (node (ref "R15") (pin "2") (pinfunction "P$2_2") (pintype "passive"))
      (node (ref "R16") (pin "2") (pinfunction "P$2_2") (pintype "passive"))
    )
    (net (code "4") (name "ADC0_CH0") (class "Default")
      (node (ref "C10") (pin "1") (pinfunction "P$1_1") (pintype "passive"))
      (node (ref "Q2") (pin "3") (pinfunction "D2A_3") (pintype "bidirectional"))
      (node (ref "R5") (pin "1") (pinfunction "P$1_1") (pintype "passive"))
      (node (ref "TP5") (pin "TP") (pinfunction "TP_TP") (pintype "input"))
    )
    (net (code "5") (name "ADC0_CH1") (class "Default")
      (node (ref "C12") (pin "2") (pinfunction "P$2_2") (pintype "passive"))
      (node (ref "R19") (pin "1") (pinfunction "P$1_1") (pintype "passive"))
      (node (ref "U3") (pin "7") (pinfunction "OUTB_7") (pintype "bidirectional"))
    )
    (net (code "6") (name "ADC1_CH0") (class "Default")
      (node (ref "C11") (pin "1") (pinfunction "P$1_1") (pintype "passive"))
      (node (ref "Q2") (pin "7") (pinfunction "D1B_7") (pintype "bidirectional"))
      (node (ref "R6") (pin "1") (pinfunction "P$1_1") (pintype "passive"))
      (node (ref "TP7") (pin "TP") (pinfunction "TP_TP") (pintype "input"))
    )
    (net (code "7") (name "ADC1_CH1") (class "Default")
      (node (ref "R32") (pin "1") (pinfunction "P$1_1") (pintype "passive"))
      (node (ref "TP6") (pin "TP") (pinfunction "TP_TP") (pintype "input"))
      (node (ref "U2") (pin "1") (pinfunction "OUTA_1") (pintype "bidirectional"))
      (node (ref "U2") (pin "2") (pinfunction "-INA_2") (pintype "bidirectional"))
    )
    (net (code "8") (name "ADIG_SP1") (class "Default")
      (node (ref "CON1") (pin "163") (pinfunction "163_163") (pintype "bidirectional"))
      (node (ref "TP12") (pin "TP") (pinfunction "TP_TP") (pintype "input"))
    )
    (net (code "9") (name "ADIG_SP2") (class "Default")
      (node (ref "CON1") (pin "164") (pinfunction "164_164") (pintype "bidirectional"))
      (node (ref "TP13") (pin "TP") (pinfunction "TP_TP") (pintype "input"))
    )
    (net (code "10") (name "ADIG_SP3") (class "Default")
      (node (ref "CON1") (pin "165") (pinfunction "165_165") (pintype "bidirectional"))
      (node (ref "TP14") (pin "TP") (pinfunction "TP_TP") (pintype "input"))
    )
    (net (code "11") (name "ADIG_SP4") (class "Default")
      (node (ref "CON1") (pin "166") (pinfunction "166_166") (pintype "bidirectional"))
      (node (ref "TP15") (pin "TP") (pinfunction "TP_TP") (pintype "input"))
    )
    (net (code "12") (name "ADIG_SP5") (class "Default")
      (node (ref "CON1") (pin "167") (pinfunction "167_167") (pintype "bidirectional"))
      (node (ref "TP16") (pin "TP") (pinfunction "TP_TP") (pintype "input"))
    )
    (net (code "13") (name "ADIG_SP6") (class "Default")
      (node (ref "CON1") (pin "168") (pinfunction "168_168") (pintype "bidirectional"))
      (node (ref "TP17") (pin "TP") (pinfunction "TP_TP") (pintype "input"))
    )
    (net (code "14") (name "ANIN0") (class "Default")
      (node (ref "CON1") (pin "140") (pinfunction "140_140") (pintype "bidirectional"))
      (node (ref "CON6") (pin "3") (pinfunction "3_3") (pintype "passive"))
      (node (ref "R4") (pin "2") (pinfunction "P$2_2") (pintype "passive"))
    )
    (net (code "15") (name "ANIN1") (class "Default")
      (node (ref "CON1") (pin "139") (pinfunction "139_139") (pintype "bidirectional"))
      (node (ref "CON6") (pin "4") (pinfunction "4_4") (pintype "passive"))
    )
    (net (code "16") (name "ANIN4") (class "Default")
      (node (ref "CON1") (pin "142") (pinfunction "142_142") (pintype "bidirectional"))
      (node (ref "CON6") (pin "5") (pinfunction "5_5") (pintype "passive"))
      (node (ref "R5") (pin "2") (pinfunction "P$2_2") (pintype "passive"))
    )
    (net (code "17") (name "ANIN5") (class "Default")
      (node (ref "CON1") (pin "141") (pinfunction "141_141") (pintype "bidirectional"))
      (node (ref "CON6") (pin "6") (pinfunction "6_6") (pintype "passive"))
    )
    (net (code "18") (name "ANIN6") (class "Default")
      (node (ref "CON1") (pin "144") (pinfunction "144_144") (pintype "bidirectional"))
      (node (ref "CON6") (pin "7") (pinfunction "7_7") (pintype "passive"))
      (node (ref "R6") (pin "2") (pinfunction "P$2_2") (pintype "passive"))
    )
    (net (code "19") (name "ANIN7") (class "Default")
      (node (ref "CON1") (pin "143") (pinfunction "143_143") (pintype "bidirectional"))
      (node (ref "CON6") (pin "8") (pinfunction "8_8") (pintype "passive"))
    )
    (net (code "20") (name "ANIN8") (class "Default")
      (node (ref "CON1") (pin "146") (pinfunction "146_146") (pintype "bidirectional"))
      (node (ref "CON6") (pin "9") (pinfunction "9_9") (pintype "passive"))
      (node (ref "R32") (pin "2") (pinfunction "P$2_2") (pintype "passive"))
    )
    (net (code "21") (name "ANIN9") (class "Default")
      (node (ref "CON1") (pin "145") (pinfunction "145_145") (pintype "bidirectional"))
      (node (ref "CON6") (pin "10") (pinfunction "10_10") (pintype "passive"))
    )
    (net (code "22") (name "ANMUX_1") (class "Default")
      (node (ref "U1") (pin "1") (pinfunction "COMMON_1") (pintype "bidirectional"))
      (node (ref "U13") (pin "9") (pinfunction "I0_9") (pintype "bidirectional"))
    )
    (net (code "23") (name "ANMUX_2") (class "Default")
      (node (ref "U13") (pin "8") (pinfunction "I1_8") (pintype "bidirectional"))
      (node (ref "U6") (pin "1") (pinfunction "COMMON_1") (pintype "bidirectional"))
    )
    (net (code "24") (name "ANMUX_3") (class "Default")
      (node (ref "U13") (pin "7") (pinfunction "I2_7") (pintype "bidirectional"))
      (node (ref "U7") (pin "1") (pinfunction "COMMON_1") (pintype "bidirectional"))
    )
    (net (code "25") (name "ANMUX_4") (class "Default")
      (node (ref "U13") (pin "6") (pinfunction "I3_6") (pintype "bidirectional"))
      (node (ref "U8") (pin "1") (pinfunction "COMMON_1") (pintype "bidirectional"))
    )
    (net (code "26") (name "ANMUX_5") (class "Default")
      (node (ref "U13") (pin "5") (pinfunction "I4_5") (pintype "bidirectional"))
      (node (ref "U9") (pin "1") (pinfunction "COMMON_1") (pintype "bidirectional"))
    )
    (net (code "27") (name "ANMUX_6") (class "Default")
      (node (ref "U10") (pin "1") (pinfunction "COMMON_1") (pintype "bidirectional"))
      (node (ref "U13") (pin "4") (pinfunction "I5_4") (pintype "bidirectional"))
    )
    (net (code "28") (name "ANMUX_7") (class "Default")
      (node (ref "U11") (pin "1") (pinfunction "COMMON_1") (pintype "bidirectional"))
      (node (ref "U13") (pin "3") (pinfunction "I6_3") (pintype "bidirectional"))
    )
    (net (code "29") (name "ANMUX_8") (class "Default")
      (node (ref "U12") (pin "1") (pinfunction "COMMON_1") (pintype "bidirectional"))
      (node (ref "U13") (pin "2") (pinfunction "I7_2") (pintype "bidirectional"))
    )
    (net (code "30") (name "AN_AD0") (class "Default")
      (node (ref "CON1") (pin "172") (pinfunction "172_172") (pintype "bidirectional"))
      (node (ref "CON7") (pin "1") (pinfunction "1_1") (pintype "passive"))
      (node (ref "R7") (pin "2") (pinfunction "P$2_2") (pintype "passive"))
      (node (ref "U1") (pin "10") (pinfunction "S0_10") (pintype "bidirectional"))
      (node (ref "U10") (pin "10") (pinfunction "S0_10") (pintype "bidirectional"))
      (node (ref "U11") (pin "10") (pinfunction "S0_10") (pintype "bidirectional"))
      (node (ref "U12") (pin "10") (pinfunction "S0_10") (pintype "bidirectional"))
      (node (ref "U6") (pin "10") (pinfunction "S0_10") (pintype "bidirectional"))
      (node (ref "U7") (pin "10") (pinfunction "S0_10") (pintype "bidirectional"))
      (node (ref "U8") (pin "10") (pinfunction "S0_10") (pintype "bidirectional"))
      (node (ref "U9") (pin "10") (pinfunction "S0_10") (pintype "bidirectional"))
    )
    (net (code "31") (name "AN_AD1") (class "Default")
      (node (ref "CON1") (pin "171") (pinfunction "171_171") (pintype "bidirectional"))
      (node (ref "CON7") (pin "3") (pinfunction "3_3") (pintype "passive"))
      (node (ref "R8") (pin "2") (pinfunction "P$2_2") (pintype "passive"))
      (node (ref "U1") (pin "11") (pinfunction "S1_11") (pintype "bidirectional"))
      (node (ref "U10") (pin "11") (pinfunction "S1_11") (pintype "bidirectional"))
      (node (ref "U11") (pin "11") (pinfunction "S1_11") (pintype "bidirectional"))
      (node (ref "U12") (pin "11") (pinfunction "S1_11") (pintype "bidirectional"))
      (node (ref "U6") (pin "11") (pinfunction "S1_11") (pintype "bidirectional"))
      (node (ref "U7") (pin "11") (pinfunction "S1_11") (pintype "bidirectional"))
      (node (ref "U8") (pin "11") (pinfunction "S1_11") (pintype "bidirectional"))
      (node (ref "U9") (pin "11") (pinfunction "S1_11") (pintype "bidirectional"))
    )
    (net (code "32") (name "AN_AD2") (class "Default")
      (node (ref "CON1") (pin "174") (pinfunction "174_174") (pintype "bidirectional"))
      (node (ref "CON7") (pin "5") (pinfunction "5_5") (pintype "passive"))
      (node (ref "R9") (pin "2") (pinfunction "P$2_2") (pintype "passive"))
      (node (ref "U1") (pin "14") (pinfunction "S2_14") (pintype "bidirectional"))
      (node (ref "U10") (pin "14") (pinfunction "S2_14") (pintype "bidirectional"))
      (node (ref "U11") (pin "14") (pinfunction "S2_14") (pintype "bidirectional"))
      (node (ref "U12") (pin "14") (pinfunction "S2_14") (pintype "bidirectional"))
      (node (ref "U6") (pin "14") (pinfunction "S2_14") (pintype "bidirectional"))
      (node (ref "U7") (pin "14") (pinfunction "S2_14") (pintype "bidirectional"))
      (node (ref "U8") (pin "14") (pinfunction "S2_14") (pintype "bidirectional"))
      (node (ref "U9") (pin "14") (pinfunction "S2_14") (pintype "bidirectional"))
    )
    (net (code "33") (name "AN_AD3") (class "Default")
      (node (ref "CON1") (pin "173") (pinfunction "173_173") (pintype "bidirectional"))
      (node (ref "CON7") (pin "7") (pinfunction "7_7") (pintype "passive"))
      (node (ref "R10") (pin "2") (pinfunction "P$2_2") (pintype "passive"))
      (node (ref "U1") (pin "13") (pinfunction "S3_13") (pintype "bidirectional"))
      (node (ref "U10") (pin "13") (pinfunction "S3_13") (pintype "bidirectional"))
      (node (ref "U11") (pin "13") (pinfunction "S3_13") (pintype "bidirectional"))
      (node (ref "U12") (pin "13") (pinfunction "S3_13") (pintype "bidirectional"))
      (node (ref "U6") (pin "13") (pinfunction "S3_13") (pintype "bidirectional"))
      (node (ref "U7") (pin "13") (pinfunction "S3_13") (pintype "bidirectional"))
      (node (ref "U8") (pin "13") (pinfunction "S3_13") (pintype "bidirectional"))
      (node (ref "U9") (pin "13") (pinfunction "S3_13") (pintype "bidirectional"))
    )
    (net (code "34") (name "AN_AD4") (class "Default")
      (node (ref "CON1") (pin "176") (pinfunction "176_176") (pintype "bidirectional"))
      (node (ref "CON7") (pin "2") (pinfunction "2_2") (pintype "passive"))
      (node (ref "R11") (pin "2") (pinfunction "P$2_2") (pintype "passive"))
      (node (ref "U13") (pin "10") (pinfunction "S0_10") (pintype "bidirectional"))
    )
    (net (code "35") (name "AN_AD5") (class "Default")
      (node (ref "CON1") (pin "175") (pinfunction "175_175") (pintype "bidirectional"))
      (node (ref "CON7") (pin "4") (pinfunction "4_4") (pintype "passive"))
      (node (ref "R12") (pin "2") (pinfunction "P$2_2") (pintype "passive"))
      (node (ref "U13") (pin "11") (pinfunction "S1_11") (pintype "bidirectional"))
    )
    (net (code "36") (name "AN_AD6") (class "Default")
      (node (ref "CON1") (pin "178") (pinfunction "178_178") (pintype "bidirectional"))
      (node (ref "CON7") (pin "6") (pinfunction "6_6") (pintype "passive"))
      (node (ref "R13") (pin "2") (pinfunction "P$2_2") (pintype "passive"))
      (node (ref "U13") (pin "14") (pinfunction "S2_14") (pintype "bidirectional"))
    )
    (net (code "37") (name "AN_AD7") (class "Default")
      (node (ref "CON1") (pin "177") (pinfunction "177_177") (pintype "bidirectional"))
      (node (ref "CON7") (pin "8") (pinfunction "8_8") (pintype "passive"))
      (node (ref "R14") (pin "2") (pinfunction "P$2_2") (pintype "passive"))
      (node (ref "U13") (pin "13") (pinfunction "S3_13") (pintype "bidirectional"))
    )
    (net (code "38") (name "CAL_EN") (class "Default")
      (node (ref "Q4") (pin "8") (pinfunction "D2B_8") (pintype "bidirectional"))
      (node (ref "R31") (pin "2") (pinfunction "P$2_2") (pintype "passive"))
      (node (ref "R8") (pin "1") (pinfunction "P$1_1") (pintype "passive"))
    )
    (net (code "39") (name "CAL_NETWORK") (class "Default")
      (node (ref "Q4") (pin "3") (pinfunction "D2A_3") (pintype "bidirectional"))
      (node (ref "R21") (pin "2") (pinfunction "P$2_2") (pintype "passive"))
      (node (ref "R23") (pin "2") (pinfunction "P$2_2") (pintype "passive"))
      (node (ref "R27") (pin "1") (pinfunction "P$1_1") (pintype "passive"))
      (node (ref "R28") (pin "1") (pinfunction "P$1_1") (pintype "passive"))
      (node (ref "R29") (pin "1") (pinfunction "P$1_1") (pintype "passive"))
      (node (ref "TP4") (pin "TP") (pinfunction "TP_TP") (pintype "input"))
      (node (ref "U4") (pin "2") (pinfunction "1Z_2") (pintype "bidirectional"))
      (node (ref "U4") (pin "6") (pinfunction "2Z_6") (pintype "bidirectional"))
      (node (ref "U5") (pin "2") (pinfunction "1Z_2") (pintype "bidirectional"))
      (node (ref "U5") (pin "6") (pinfunction "2Z_6") (pintype "bidirectional"))
    )
    (net (code "40") (name "CNTRL0") (class "Default")
      (node (ref "R11") (pin "1") (pinfunction "P$1_1") (pintype "passive"))
      (node (ref "R46") (pin "2") (pinfunction "P$2_2") (pintype "passive"))
      (node (ref "U5") (pin "3") (pinfunction "2E_3") (pintype "bidirectional"))
    )
    (net (code "41") (name "CNTRL1") (class "Default")
      (node (ref "R12") (pin "1") (pinfunction "P$1_1") (pintype "passive"))
      (node (ref "R37") (pin "2") (pinfunction "P$2_2") (pintype "passive"))
      (node (ref "U5") (pin "7") (pinfunction "1E_7") (pintype "bidirectional"))
    )
    (net (code "42") (name "CNTRL2") (class "Default")
      (node (ref "R13") (pin "1") (pinfunction "P$1_1") (pintype "passive"))
      (node (ref "R48") (pin "2") (pinfunction "P$2_2") (pintype "passive"))
      (node (ref "U4") (pin "3") (pinfunction "2E_3") (pintype "bidirectional"))
    )
    (net (code "43") (name "CNTRL3") (class "Default")
      (node (ref "R14") (pin "1") (pinfunction "P$1_1") (pintype "passive"))
      (node (ref "R47") (pin "2") (pinfunction "P$2_2") (pintype "passive"))
      (node (ref "U4") (pin "7") (pinfunction "1E_7") (pintype "bidirectional"))
    )
    (net (code "44") (name "DUT_AN") (class "Default")
      (node (ref "CON1") (pin "170") (pinfunction "170_170") (pintype "bidirectional"))
      (node (ref "CON7") (pin "9") (pinfunction "9_9") (pintype "passive"))
      (node (ref "R4") (pin "1") (pinfunction "P$1_1") (pintype "passive"))
      (node (ref "U13") (pin "1") (pinfunction "COMMON_1") (pintype "bidirectional"))
    )
    (net (code "45") (name "G1") (class "Default")
      (node (ref "Q2") (pin "8") (pinfunction "D2B_8") (pintype "bidirectional"))
      (node (ref "R16") (pin "1") (pinfunction "P$1_1") (pintype "passive"))
      (node (ref "R9") (pin "1") (pinfunction "P$1_1") (pintype "passive"))
    )
    (net (code "46") (name "G2") (class "Default")
      (node (ref "Q2") (pin "6") (pinfunction "D1A_6") (pintype "bidirectional"))
      (node (ref "R10") (pin "1") (pinfunction "P$1_1") (pintype "passive"))
      (node (ref "R15") (pin "1") (pinfunction "P$1_1") (pintype "passive"))
    )
    (net (code "47") (name "GND") (class "Default")
      (node (ref "C1") (pin "2") (pinfunction "P$2_2") (pintype "passive"))
      (node (ref "C10") (pin "2") (pinfunction "P$2_2") (pintype "passive"))
      (node (ref "C11") (pin "2") (pinfunction "P$2_2") (pintype "passive"))
      (node (ref "C13") (pin "2") (pinfunction "P$2_2") (pintype "passive"))
      (node (ref "C14") (pin "2") (pinfunction "P$2_2") (pintype "passive"))
      (node (ref "C15") (pin "2") (pinfunction "P$2_2") (pintype "passive"))
      (node (ref "C16") (pin "1") (pinfunction "P$1_1") (pintype "passive"))
      (node (ref "C17") (pin "1") (pinfunction "P$1_1") (pintype "passive"))
      (node (ref "C2") (pin "2") (pinfunction "P$2_2") (pintype "passive"))
      (node (ref "C3") (pin "2") (pinfunction "P$2_2") (pintype "passive"))
      (node (ref "C4") (pin "2") (pinfunction "P$2_2") (pintype "passive"))
      (node (ref "C5") (pin "2") (pinfunction "P$2_2") (pintype "passive"))
      (node (ref "C6") (pin "2") (pinfunction "P$2_2") (pintype "passive"))
      (node (ref "CON1") (pin "P$1") (pinfunction "181_P$1") (pintype "bidirectional"))
      (node (ref "CON1") (pin "P$10") (pinfunction "190_P$10") (pintype "bidirectional"))
      (node (ref "CON1") (pin "P$11") (pinfunction "191_P$11") (pintype "bidirectional"))
      (node (ref "CON1") (pin "P$12") (pinfunction "192_P$12") (pintype "bidirectional"))
      (node (ref "CON1") (pin "P$2") (pinfunction "182_P$2") (pintype "bidirectional"))
      (node (ref "CON1") (pin "P$3") (pinfunction "183_P$3") (pintype "bidirectional"))
      (node (ref "CON1") (pin "P$4") (pinfunction "184_P$4") (pintype "bidirectional"))
      (node (ref "CON1") (pin "P$5") (pinfunction "185_P$5") (pintype "bidirectional"))
      (node (ref "CON1") (pin "P$6") (pinfunction "186_P$6") (pintype "bidirectional"))
      (node (ref "CON1") (pin "P$7") (pinfunction "187_P$7") (pintype "bidirectional"))
      (node (ref "CON1") (pin "P$8") (pinfunction "188_P$8") (pintype "bidirectional"))
      (node (ref "CON1") (pin "P$9") (pinfunction "189_P$9") (pintype "bidirectional"))
      (node (ref "CON6") (pin "11") (pinfunction "11_11") (pintype "passive"))
      (node (ref "CON7") (pin "11") (pinfunction "11_11") (pintype "passive"))
      (node (ref "LED2") (pin "C") (pinfunction "C_C") (pintype "passive"))
      (node (ref "LED3") (pin "C") (pinfunction "C_C") (pintype "passive"))
      (node (ref "PTH1") (pin "1") (pinfunction "1_1") (pintype "bidirectional"))
      (node (ref "PTH2") (pin "1") (pinfunction "1_1") (pintype "bidirectional"))
      (node (ref "PTH3") (pin "1") (pinfunction "1_1") (pintype "bidirectional"))
      (node (ref "PTH4") (pin "1") (pinfunction "1_1") (pintype "bidirectional"))
      (node (ref "PTH5") (pin "1") (pinfunction "1_1") (pintype "bidirectional"))
      (node (ref "PTH6") (pin "1") (pinfunction "1_1") (pintype "bidirectional"))
      (node (ref "PTH7") (pin "1") (pinfunction "1_1") (pintype "bidirectional"))
      (node (ref "PTH8") (pin "1") (pinfunction "1_1") (pintype "bidirectional"))
      (node (ref "R17") (pin "2") (pinfunction "P$2_2") (pintype "passive"))
      (node (ref "R18") (pin "2") (pinfunction "P$2_2") (pintype "passive"))
      (node (ref "R24") (pin "2") (pinfunction "P$2_2") (pintype "passive"))
      (node (ref "R30") (pin "1") (pinfunction "P$1_1") (pintype "passive"))
      (node (ref "R31") (pin "1") (pinfunction "P$1_1") (pintype "passive"))
      (node (ref "R33") (pin "2") (pinfunction "P$2_2") (pintype "passive"))
      (node (ref "R34") (pin "2") (pinfunction "P$2_2") (pintype "passive"))
      (node (ref "R35") (pin "2") (pinfunction "P$2_2") (pintype "passive"))
      (node (ref "R36") (pin "2") (pinfunction "P$2_2") (pintype "passive"))
      (node (ref "R37") (pin "1") (pinfunction "P$1_1") (pintype "passive"))
      (node (ref "R46") (pin "1") (pinfunction "P$1_1") (pintype "passive"))
      (node (ref "R47") (pin "1") (pinfunction "P$1_1") (pintype "passive"))
      (node (ref "R48") (pin "1") (pinfunction "P$1_1") (pintype "passive"))
      (node (ref "U1") (pin "12") (pinfunction "GND_12") (pintype "bidirectional"))
      (node (ref "U10") (pin "12") (pinfunction "GND_12") (pintype "bidirectional"))
      (node (ref "U11") (pin "12") (pinfunction "GND_12") (pintype "bidirectional"))
      (node (ref "U12") (pin "12") (pinfunction "GND_12") (pintype "bidirectional"))
      (node (ref "U13") (pin "12") (pinfunction "GND_12") (pintype "bidirectional"))
      (node (ref "U13") (pin "20") (pinfunction "I11_20") (pintype "bidirectional"))
      (node (ref "U2") (pin "4") (pinfunction "V-_4") (pintype "bidirectional"))
      (node (ref "U3") (pin "4") (pinfunction "V-_4") (pintype "bidirectional"))
      (node (ref "U4") (pin "4") (pinfunction "GND_4") (pintype "bidirectional"))
      (node (ref "U5") (pin "4") (pinfunction "GND_4") (pintype "bidirectional"))
      (node (ref "U6") (pin "12") (pinfunction "GND_12") (pintype "bidirectional"))
      (node (ref "U7") (pin "12") (pinfunction "GND_12") (pintype "bidirectional"))
      (node (ref "U8") (pin "12") (pinfunction "GND_12") (pintype "bidirectional"))
      (node (ref "U9") (pin "12") (pinfunction "GND_12") (pintype "bidirectional"))
    )
    (net (code "48") (name "IO0") (class "Default")
      (node (ref "CON1") (pin "6") (pinfunction "6_6") (pintype "bidirectional"))
      (node (ref "CON2") (pin "1") (pinfunction "1_1") (pintype "passive"))
      (node (ref "U1") (pin "9") (pinfunction "I0_9") (pintype "bidirectional"))
    )
    (net (code "49") (name "IO1") (class "Default")
      (node (ref "CON1") (pin "5") (pinfunction "5_5") (pintype "bidirectional"))
      (node (ref "CON2") (pin "2") (pinfunction "2_2") (pintype "passive"))
      (node (ref "U1") (pin "8") (pinfunction "I1_8") (pintype "bidirectional"))
    )
    (net (code "50") (name "IO2") (class "Default")
      (node (ref "CON1") (pin "8") (pinfunction "8_8") (pintype "bidirectional"))
      (node (ref "CON2") (pin "3") (pinfunction "3_3") (pintype "passive"))
      (node (ref "U1") (pin "7") (pinfunction "I2_7") (pintype "bidirectional"))
    )
    (net (code "51") (name "IO3") (class "Default")
      (node (ref "CON1") (pin "7") (pinfunction "7_7") (pintype "bidirectional"))
      (node (ref "CON2") (pin "4") (pinfunction "4_4") (pintype "passive"))
      (node (ref "U1") (pin "6") (pinfunction "I3_6") (pintype "bidirectional"))
    )
    (net (code "52") (name "IO4") (class "Default")
      (node (ref "CON1") (pin "10") (pinfunction "10_10") (pintype "bidirectional"))
      (node (ref "CON2") (pin "5") (pinfunction "5_5") (pintype "passive"))
      (node (ref "U1") (pin "5") (pinfunction "I4_5") (pintype "bidirectional"))
    )
    (net (code "53") (name "IO5") (class "Default")
      (node (ref "CON1") (pin "9") (pinfunction "9_9") (pintype "bidirectional"))
      (node (ref "CON2") (pin "6") (pinfunction "6_6") (pintype "passive"))
      (node (ref "U1") (pin "4") (pinfunction "I5_4") (pintype "bidirectional"))
    )
    (net (code "54") (name "IO6") (class "Default")
      (node (ref "CON1") (pin "12") (pinfunction "12_12") (pintype "bidirectional"))
      (node (ref "CON2") (pin "7") (pinfunction "7_7") (pintype "passive"))
      (node (ref "U1") (pin "3") (pinfunction "I6_3") (pintype "bidirectional"))
    )
    (net (code "55") (name "IO7") (class "Default")
      (node (ref "CON1") (pin "11") (pinfunction "11_11") (pintype "bidirectional"))
      (node (ref "CON2") (pin "8") (pinfunction "8_8") (pintype "passive"))
      (node (ref "U1") (pin "2") (pinfunction "I7_2") (pintype "bidirectional"))
    )
    (net (code "56") (name "IO8") (class "Default")
      (node (ref "CON1") (pin "14") (pinfunction "14_14") (pintype "bidirectional"))
      (node (ref "CON2") (pin "9") (pinfunction "9_9") (pintype "passive"))
      (node (ref "U1") (pin "23") (pinfunction "I8_23") (pintype "bidirectional"))
    )
    (net (code "57") (name "IO9") (class "Default")
      (node (ref "CON1") (pin "13") (pinfunction "13_13") (pintype "bidirectional"))
      (node (ref "CON2") (pin "10") (pinfunction "10_10") (pintype "passive"))
      (node (ref "U1") (pin "22") (pinfunction "I9_22") (pintype "bidirectional"))
    )
    (net (code "58") (name "IO10") (class "Default")
      (node (ref "CON1") (pin "16") (pinfunction "16_16") (pintype "bidirectional"))
      (node (ref "CON2") (pin "11") (pinfunction "11_11") (pintype "passive"))
      (node (ref "U1") (pin "21") (pinfunction "I10_21") (pintype "bidirectional"))
    )
    (net (code "59") (name "IO11") (class "Default")
      (node (ref "CON1") (pin "15") (pinfunction "15_15") (pintype "bidirectional"))
      (node (ref "CON2") (pin "12") (pinfunction "12_12") (pintype "passive"))
      (node (ref "U1") (pin "20") (pinfunction "I11_20") (pintype "bidirectional"))
    )
    (net (code "60") (name "IO12") (class "Default")
      (node (ref "CON1") (pin "18") (pinfunction "18_18") (pintype "bidirectional"))
      (node (ref "CON2") (pin "13") (pinfunction "13_13") (pintype "passive"))
      (node (ref "U1") (pin "19") (pinfunction "I12_19") (pintype "bidirectional"))
    )
    (net (code "61") (name "IO13") (class "Default")
      (node (ref "CON1") (pin "17") (pinfunction "17_17") (pintype "bidirectional"))
      (node (ref "CON2") (pin "14") (pinfunction "14_14") (pintype "passive"))
      (node (ref "U1") (pin "18") (pinfunction "I13_18") (pintype "bidirectional"))
    )
    (net (code "62") (name "IO14") (class "Default")
      (node (ref "CON1") (pin "20") (pinfunction "20_20") (pintype "bidirectional"))
      (node (ref "CON2") (pin "15") (pinfunction "15_15") (pintype "passive"))
      (node (ref "U1") (pin "17") (pinfunction "I14_17") (pintype "bidirectional"))
    )
    (net (code "63") (name "IO15") (class "Default")
      (node (ref "CON1") (pin "19") (pinfunction "19_19") (pintype "bidirectional"))
      (node (ref "CON2") (pin "16") (pinfunction "16_16") (pintype "passive"))
      (node (ref "U1") (pin "16") (pinfunction "I15_16") (pintype "bidirectional"))
    )
    (net (code "64") (name "IO16") (class "Default")
      (node (ref "CON1") (pin "22") (pinfunction "22_22") (pintype "bidirectional"))
      (node (ref "CON2") (pin "17") (pinfunction "17_17") (pintype "passive"))
      (node (ref "U6") (pin "9") (pinfunction "I0_9") (pintype "bidirectional"))
    )
    (net (code "65") (name "IO17") (class "Default")
      (node (ref "CON1") (pin "21") (pinfunction "21_21") (pintype "bidirectional"))
      (node (ref "CON2") (pin "18") (pinfunction "18_18") (pintype "passive"))
      (node (ref "U6") (pin "8") (pinfunction "I1_8") (pintype "bidirectional"))
    )
    (net (code "66") (name "IO18") (class "Default")
      (node (ref "CON1") (pin "24") (pinfunction "24_24") (pintype "bidirectional"))
      (node (ref "CON2") (pin "19") (pinfunction "19_19") (pintype "passive"))
      (node (ref "U6") (pin "7") (pinfunction "I2_7") (pintype "bidirectional"))
    )
    (net (code "67") (name "IO19") (class "Default")
      (node (ref "CON1") (pin "23") (pinfunction "23_23") (pintype "bidirectional"))
      (node (ref "CON2") (pin "20") (pinfunction "20_20") (pintype "passive"))
      (node (ref "U6") (pin "6") (pinfunction "I3_6") (pintype "bidirectional"))
    )
    (net (code "68") (name "IO20") (class "Default")
      (node (ref "CON1") (pin "26") (pinfunction "26_26") (pintype "bidirectional"))
      (node (ref "CON2") (pin "21") (pinfunction "21_21") (pintype "passive"))
      (node (ref "U6") (pin "5") (pinfunction "I4_5") (pintype "bidirectional"))
    )
    (net (code "69") (name "IO21") (class "Default")
      (node (ref "CON1") (pin "25") (pinfunction "25_25") (pintype "bidirectional"))
      (node (ref "CON2") (pin "22") (pinfunction "22_22") (pintype "passive"))
      (node (ref "U6") (pin "4") (pinfunction "I5_4") (pintype "bidirectional"))
    )
    (net (code "70") (name "IO22") (class "Default")
      (node (ref "CON1") (pin "28") (pinfunction "28_28") (pintype "bidirectional"))
      (node (ref "CON2") (pin "23") (pinfunction "23_23") (pintype "passive"))
      (node (ref "U6") (pin "3") (pinfunction "I6_3") (pintype "bidirectional"))
    )
    (net (code "71") (name "IO23") (class "Default")
      (node (ref "CON1") (pin "27") (pinfunction "27_27") (pintype "bidirectional"))
      (node (ref "CON2") (pin "24") (pinfunction "24_24") (pintype "passive"))
      (node (ref "U6") (pin "2") (pinfunction "I7_2") (pintype "bidirectional"))
    )
    (net (code "72") (name "IO24") (class "Default")
      (node (ref "CON1") (pin "30") (pinfunction "30_30") (pintype "bidirectional"))
      (node (ref "CON2") (pin "25") (pinfunction "25_25") (pintype "passive"))
      (node (ref "U6") (pin "23") (pinfunction "I8_23") (pintype "bidirectional"))
    )
    (net (code "73") (name "IO25") (class "Default")
      (node (ref "CON1") (pin "29") (pinfunction "29_29") (pintype "bidirectional"))
      (node (ref "CON2") (pin "26") (pinfunction "26_26") (pintype "passive"))
      (node (ref "U6") (pin "22") (pinfunction "I9_22") (pintype "bidirectional"))
    )
    (net (code "74") (name "IO26") (class "Default")
      (node (ref "CON1") (pin "32") (pinfunction "32_32") (pintype "bidirectional"))
      (node (ref "CON2") (pin "27") (pinfunction "27_27") (pintype "passive"))
      (node (ref "U6") (pin "21") (pinfunction "I10_21") (pintype "bidirectional"))
    )
    (net (code "75") (name "IO27") (class "Default")
      (node (ref "CON1") (pin "31") (pinfunction "31_31") (pintype "bidirectional"))
      (node (ref "CON2") (pin "28") (pinfunction "28_28") (pintype "passive"))
      (node (ref "U6") (pin "20") (pinfunction "I11_20") (pintype "bidirectional"))
    )
    (net (code "76") (name "IO28") (class "Default")
      (node (ref "CON1") (pin "34") (pinfunction "34_34") (pintype "bidirectional"))
      (node (ref "CON2") (pin "29") (pinfunction "29_29") (pintype "passive"))
      (node (ref "U6") (pin "19") (pinfunction "I12_19") (pintype "bidirectional"))
    )
    (net (code "77") (name "IO29") (class "Default")
      (node (ref "CON1") (pin "33") (pinfunction "33_33") (pintype "bidirectional"))
      (node (ref "CON2") (pin "30") (pinfunction "30_30") (pintype "passive"))
      (node (ref "U6") (pin "18") (pinfunction "I13_18") (pintype "bidirectional"))
    )
    (net (code "78") (name "IO30") (class "Default")
      (node (ref "CON1") (pin "36") (pinfunction "36_36") (pintype "bidirectional"))
      (node (ref "CON2") (pin "31") (pinfunction "31_31") (pintype "passive"))
      (node (ref "U6") (pin "17") (pinfunction "I14_17") (pintype "bidirectional"))
    )
    (net (code "79") (name "IO31") (class "Default")
      (node (ref "CON1") (pin "35") (pinfunction "35_35") (pintype "bidirectional"))
      (node (ref "CON2") (pin "32") (pinfunction "32_32") (pintype "passive"))
      (node (ref "U6") (pin "16") (pinfunction "I15_16") (pintype "bidirectional"))
    )
    (net (code "80") (name "IO32") (class "Default")
      (node (ref "CON1") (pin "38") (pinfunction "38_38") (pintype "bidirectional"))
      (node (ref "CON3") (pin "1") (pinfunction "1_1") (pintype "passive"))
      (node (ref "U7") (pin "9") (pinfunction "I0_9") (pintype "bidirectional"))
    )
    (net (code "81") (name "IO33") (class "Default")
      (node (ref "CON1") (pin "37") (pinfunction "37_37") (pintype "bidirectional"))
      (node (ref "CON3") (pin "2") (pinfunction "2_2") (pintype "passive"))
      (node (ref "U7") (pin "8") (pinfunction "I1_8") (pintype "bidirectional"))
    )
    (net (code "82") (name "IO34") (class "Default")
      (node (ref "CON1") (pin "40") (pinfunction "40_40") (pintype "bidirectional"))
      (node (ref "CON3") (pin "3") (pinfunction "3_3") (pintype "passive"))
      (node (ref "U7") (pin "7") (pinfunction "I2_7") (pintype "bidirectional"))
    )
    (net (code "83") (name "IO35") (class "Default")
      (node (ref "CON1") (pin "39") (pinfunction "39_39") (pintype "bidirectional"))
      (node (ref "CON3") (pin "4") (pinfunction "4_4") (pintype "passive"))
      (node (ref "U7") (pin "6") (pinfunction "I3_6") (pintype "bidirectional"))
    )
    (net (code "84") (name "IO36") (class "Default")
      (node (ref "CON1") (pin "42") (pinfunction "42_42") (pintype "bidirectional"))
      (node (ref "CON3") (pin "5") (pinfunction "5_5") (pintype "passive"))
      (node (ref "U7") (pin "5") (pinfunction "I4_5") (pintype "bidirectional"))
    )
    (net (code "85") (name "IO37") (class "Default")
      (node (ref "CON1") (pin "41") (pinfunction "41_41") (pintype "bidirectional"))
      (node (ref "CON3") (pin "6") (pinfunction "6_6") (pintype "passive"))
      (node (ref "U7") (pin "4") (pinfunction "I5_4") (pintype "bidirectional"))
    )
    (net (code "86") (name "IO38") (class "Default")
      (node (ref "CON1") (pin "44") (pinfunction "44_44") (pintype "bidirectional"))
      (node (ref "CON3") (pin "7") (pinfunction "7_7") (pintype "passive"))
      (node (ref "U7") (pin "3") (pinfunction "I6_3") (pintype "bidirectional"))
    )
    (net (code "87") (name "IO39") (class "Default")
      (node (ref "CON1") (pin "43") (pinfunction "43_43") (pintype "bidirectional"))
      (node (ref "CON3") (pin "8") (pinfunction "8_8") (pintype "passive"))
      (node (ref "U7") (pin "2") (pinfunction "I7_2") (pintype "bidirectional"))
    )
    (net (code "88") (name "IO40") (class "Default")
      (node (ref "CON1") (pin "46") (pinfunction "46_46") (pintype "bidirectional"))
      (node (ref "CON3") (pin "9") (pinfunction "9_9") (pintype "passive"))
      (node (ref "U7") (pin "23") (pinfunction "I8_23") (pintype "bidirectional"))
    )
    (net (code "89") (name "IO41") (class "Default")
      (node (ref "CON1") (pin "45") (pinfunction "45_45") (pintype "bidirectional"))
      (node (ref "CON3") (pin "10") (pinfunction "10_10") (pintype "passive"))
      (node (ref "U7") (pin "22") (pinfunction "I9_22") (pintype "bidirectional"))
    )
    (net (code "90") (name "IO42") (class "Default")
      (node (ref "CON1") (pin "48") (pinfunction "48_48") (pintype "bidirectional"))
      (node (ref "CON3") (pin "11") (pinfunction "11_11") (pintype "passive"))
      (node (ref "U7") (pin "21") (pinfunction "I10_21") (pintype "bidirectional"))
    )
    (net (code "91") (name "IO43") (class "Default")
      (node (ref "CON1") (pin "47") (pinfunction "47_47") (pintype "bidirectional"))
      (node (ref "CON3") (pin "12") (pinfunction "12_12") (pintype "passive"))
      (node (ref "U7") (pin "20") (pinfunction "I11_20") (pintype "bidirectional"))
    )
    (net (code "92") (name "IO44") (class "Default")
      (node (ref "CON1") (pin "50") (pinfunction "50_50") (pintype "bidirectional"))
      (node (ref "CON3") (pin "13") (pinfunction "13_13") (pintype "passive"))
      (node (ref "U7") (pin "19") (pinfunction "I12_19") (pintype "bidirectional"))
    )
    (net (code "93") (name "IO45") (class "Default")
      (node (ref "CON1") (pin "49") (pinfunction "49_49") (pintype "bidirectional"))
      (node (ref "CON3") (pin "14") (pinfunction "14_14") (pintype "passive"))
      (node (ref "U7") (pin "18") (pinfunction "I13_18") (pintype "bidirectional"))
    )
    (net (code "94") (name "IO46") (class "Default")
      (node (ref "CON1") (pin "52") (pinfunction "52_52") (pintype "bidirectional"))
      (node (ref "CON3") (pin "15") (pinfunction "15_15") (pintype "passive"))
      (node (ref "U7") (pin "17") (pinfunction "I14_17") (pintype "bidirectional"))
    )
    (net (code "95") (name "IO47") (class "Default")
      (node (ref "CON1") (pin "51") (pinfunction "51_51") (pintype "bidirectional"))
      (node (ref "CON3") (pin "16") (pinfunction "16_16") (pintype "passive"))
      (node (ref "U7") (pin "16") (pinfunction "I15_16") (pintype "bidirectional"))
    )
    (net (code "96") (name "IO48") (class "Default")
      (node (ref "CON1") (pin "54") (pinfunction "54_54") (pintype "bidirectional"))
      (node (ref "CON3") (pin "17") (pinfunction "17_17") (pintype "passive"))
      (node (ref "U8") (pin "9") (pinfunction "I0_9") (pintype "bidirectional"))
    )
    (net (code "97") (name "IO49") (class "Default")
      (node (ref "CON1") (pin "53") (pinfunction "53_53") (pintype "bidirectional"))
      (node (ref "CON3") (pin "18") (pinfunction "18_18") (pintype "passive"))
      (node (ref "U8") (pin "8") (pinfunction "I1_8") (pintype "bidirectional"))
    )
    (net (code "98") (name "IO50") (class "Default")
      (node (ref "CON1") (pin "56") (pinfunction "56_56") (pintype "bidirectional"))
      (node (ref "CON3") (pin "19") (pinfunction "19_19") (pintype "passive"))
      (node (ref "U8") (pin "7") (pinfunction "I2_7") (pintype "bidirectional"))
    )
    (net (code "99") (name "IO51") (class "Default")
      (node (ref "CON1") (pin "55") (pinfunction "55_55") (pintype "bidirectional"))
      (node (ref "CON3") (pin "20") (pinfunction "20_20") (pintype "passive"))
      (node (ref "U8") (pin "6") (pinfunction "I3_6") (pintype "bidirectional"))
    )
    (net (code "100") (name "IO52") (class "Default")
      (node (ref "CON1") (pin "58") (pinfunction "58_58") (pintype "bidirectional"))
      (node (ref "CON3") (pin "21") (pinfunction "21_21") (pintype "passive"))
      (node (ref "U8") (pin "5") (pinfunction "I4_5") (pintype "bidirectional"))
    )
    (net (code "101") (name "IO53") (class "Default")
      (node (ref "CON1") (pin "57") (pinfunction "57_57") (pintype "bidirectional"))
      (node (ref "CON3") (pin "22") (pinfunction "22_22") (pintype "passive"))
      (node (ref "U8") (pin "4") (pinfunction "I5_4") (pintype "bidirectional"))
    )
    (net (code "102") (name "IO54") (class "Default")
      (node (ref "CON1") (pin "60") (pinfunction "60_60") (pintype "bidirectional"))
      (node (ref "CON3") (pin "23") (pinfunction "23_23") (pintype "passive"))
      (node (ref "U8") (pin "3") (pinfunction "I6_3") (pintype "bidirectional"))
    )
    (net (code "103") (name "IO55") (class "Default")
      (node (ref "CON1") (pin "59") (pinfunction "59_59") (pintype "bidirectional"))
      (node (ref "CON3") (pin "24") (pinfunction "24_24") (pintype "passive"))
      (node (ref "U8") (pin "2") (pinfunction "I7_2") (pintype "bidirectional"))
    )
    (net (code "104") (name "IO56") (class "Default")
      (node (ref "CON1") (pin "62") (pinfunction "62_62") (pintype "bidirectional"))
      (node (ref "CON3") (pin "25") (pinfunction "25_25") (pintype "passive"))
      (node (ref "U8") (pin "23") (pinfunction "I8_23") (pintype "bidirectional"))
    )
    (net (code "105") (name "IO57") (class "Default")
      (node (ref "CON1") (pin "61") (pinfunction "61_61") (pintype "bidirectional"))
      (node (ref "CON3") (pin "26") (pinfunction "26_26") (pintype "passive"))
      (node (ref "U8") (pin "22") (pinfunction "I9_22") (pintype "bidirectional"))
    )
    (net (code "106") (name "IO58") (class "Default")
      (node (ref "CON1") (pin "64") (pinfunction "64_64") (pintype "bidirectional"))
      (node (ref "CON3") (pin "27") (pinfunction "27_27") (pintype "passive"))
      (node (ref "U8") (pin "21") (pinfunction "I10_21") (pintype "bidirectional"))
    )
    (net (code "107") (name "IO59") (class "Default")
      (node (ref "CON1") (pin "63") (pinfunction "63_63") (pintype "bidirectional"))
      (node (ref "CON3") (pin "28") (pinfunction "28_28") (pintype "passive"))
      (node (ref "U8") (pin "20") (pinfunction "I11_20") (pintype "bidirectional"))
    )
    (net (code "108") (name "IO60") (class "Default")
      (node (ref "CON1") (pin "66") (pinfunction "66_66") (pintype "bidirectional"))
      (node (ref "CON3") (pin "29") (pinfunction "29_29") (pintype "passive"))
      (node (ref "U8") (pin "19") (pinfunction "I12_19") (pintype "bidirectional"))
    )
    (net (code "109") (name "IO61") (class "Default")
      (node (ref "CON1") (pin "65") (pinfunction "65_65") (pintype "bidirectional"))
      (node (ref "CON3") (pin "30") (pinfunction "30_30") (pintype "passive"))
      (node (ref "U8") (pin "18") (pinfunction "I13_18") (pintype "bidirectional"))
    )
    (net (code "110") (name "IO62") (class "Default")
      (node (ref "CON1") (pin "68") (pinfunction "68_68") (pintype "bidirectional"))
      (node (ref "CON3") (pin "31") (pinfunction "31_31") (pintype "passive"))
      (node (ref "U8") (pin "17") (pinfunction "I14_17") (pintype "bidirectional"))
    )
    (net (code "111") (name "IO63") (class "Default")
      (node (ref "CON1") (pin "67") (pinfunction "67_67") (pintype "bidirectional"))
      (node (ref "CON3") (pin "32") (pinfunction "32_32") (pintype "passive"))
      (node (ref "U8") (pin "16") (pinfunction "I15_16") (pintype "bidirectional"))
    )
    (net (code "112") (name "IO64") (class "Default")
      (node (ref "CON1") (pin "70") (pinfunction "70_70") (pintype "bidirectional"))
      (node (ref "CON4") (pin "1") (pinfunction "1_1") (pintype "passive"))
      (node (ref "U9") (pin "9") (pinfunction "I0_9") (pintype "bidirectional"))
    )
    (net (code "113") (name "IO65") (class "Default")
      (node (ref "CON1") (pin "69") (pinfunction "69_69") (pintype "bidirectional"))
      (node (ref "CON4") (pin "2") (pinfunction "2_2") (pintype "passive"))
      (node (ref "U9") (pin "8") (pinfunction "I1_8") (pintype "bidirectional"))
    )
    (net (code "114") (name "IO66") (class "Default")
      (node (ref "CON1") (pin "72") (pinfunction "72_72") (pintype "bidirectional"))
      (node (ref "CON4") (pin "3") (pinfunction "3_3") (pintype "passive"))
      (node (ref "U9") (pin "7") (pinfunction "I2_7") (pintype "bidirectional"))
    )
    (net (code "115") (name "IO67") (class "Default")
      (node (ref "CON1") (pin "71") (pinfunction "71_71") (pintype "bidirectional"))
      (node (ref "CON4") (pin "4") (pinfunction "4_4") (pintype "passive"))
      (node (ref "U9") (pin "6") (pinfunction "I3_6") (pintype "bidirectional"))
    )
    (net (code "116") (name "IO68") (class "Default")
      (node (ref "CON1") (pin "74") (pinfunction "74_74") (pintype "bidirectional"))
      (node (ref "CON4") (pin "5") (pinfunction "5_5") (pintype "passive"))
      (node (ref "U9") (pin "5") (pinfunction "I4_5") (pintype "bidirectional"))
    )
    (net (code "117") (name "IO69") (class "Default")
      (node (ref "CON1") (pin "73") (pinfunction "73_73") (pintype "bidirectional"))
      (node (ref "CON4") (pin "6") (pinfunction "6_6") (pintype "passive"))
      (node (ref "U9") (pin "4") (pinfunction "I5_4") (pintype "bidirectional"))
    )
    (net (code "118") (name "IO70") (class "Default")
      (node (ref "CON1") (pin "76") (pinfunction "76_76") (pintype "bidirectional"))
      (node (ref "CON4") (pin "7") (pinfunction "7_7") (pintype "passive"))
      (node (ref "U9") (pin "3") (pinfunction "I6_3") (pintype "bidirectional"))
    )
    (net (code "119") (name "IO71") (class "Default")
      (node (ref "CON1") (pin "75") (pinfunction "75_75") (pintype "bidirectional"))
      (node (ref "CON4") (pin "8") (pinfunction "8_8") (pintype "passive"))
      (node (ref "U9") (pin "2") (pinfunction "I7_2") (pintype "bidirectional"))
    )
    (net (code "120") (name "IO72") (class "Default")
      (node (ref "CON1") (pin "78") (pinfunction "78_78") (pintype "bidirectional"))
      (node (ref "CON4") (pin "9") (pinfunction "9_9") (pintype "passive"))
      (node (ref "U9") (pin "23") (pinfunction "I8_23") (pintype "bidirectional"))
    )
    (net (code "121") (name "IO73") (class "Default")
      (node (ref "CON1") (pin "77") (pinfunction "77_77") (pintype "bidirectional"))
      (node (ref "CON4") (pin "10") (pinfunction "10_10") (pintype "passive"))
      (node (ref "U9") (pin "22") (pinfunction "I9_22") (pintype "bidirectional"))
    )
    (net (code "122") (name "IO74") (class "Default")
      (node (ref "CON1") (pin "80") (pinfunction "80_80") (pintype "bidirectional"))
      (node (ref "CON4") (pin "11") (pinfunction "11_11") (pintype "passive"))
      (node (ref "U9") (pin "21") (pinfunction "I10_21") (pintype "bidirectional"))
    )
    (net (code "123") (name "IO75") (class "Default")
      (node (ref "CON1") (pin "79") (pinfunction "79_79") (pintype "bidirectional"))
      (node (ref "CON4") (pin "12") (pinfunction "12_12") (pintype "passive"))
      (node (ref "U9") (pin "20") (pinfunction "I11_20") (pintype "bidirectional"))
    )
    (net (code "124") (name "IO76") (class "Default")
      (node (ref "CON1") (pin "82") (pinfunction "82_82") (pintype "bidirectional"))
      (node (ref "CON4") (pin "13") (pinfunction "13_13") (pintype "passive"))
      (node (ref "U9") (pin "19") (pinfunction "I12_19") (pintype "bidirectional"))
    )
    (net (code "125") (name "IO77") (class "Default")
      (node (ref "CON1") (pin "81") (pinfunction "81_81") (pintype "bidirectional"))
      (node (ref "CON4") (pin "14") (pinfunction "14_14") (pintype "passive"))
      (node (ref "U9") (pin "18") (pinfunction "I13_18") (pintype "bidirectional"))
    )
    (net (code "126") (name "IO78") (class "Default")
      (node (ref "CON1") (pin "84") (pinfunction "84_84") (pintype "bidirectional"))
      (node (ref "CON4") (pin "15") (pinfunction "15_15") (pintype "passive"))
      (node (ref "U9") (pin "17") (pinfunction "I14_17") (pintype "bidirectional"))
    )
    (net (code "127") (name "IO79") (class "Default")
      (node (ref "CON1") (pin "83") (pinfunction "83_83") (pintype "bidirectional"))
      (node (ref "CON4") (pin "16") (pinfunction "16_16") (pintype "passive"))
      (node (ref "U9") (pin "16") (pinfunction "I15_16") (pintype "bidirectional"))
    )
    (net (code "128") (name "IO80") (class "Default")
      (node (ref "CON1") (pin "86") (pinfunction "86_86") (pintype "bidirectional"))
      (node (ref "CON4") (pin "17") (pinfunction "17_17") (pintype "passive"))
      (node (ref "U10") (pin "9") (pinfunction "I0_9") (pintype "bidirectional"))
    )
    (net (code "129") (name "IO81") (class "Default")
      (node (ref "CON1") (pin "85") (pinfunction "85_85") (pintype "bidirectional"))
      (node (ref "CON4") (pin "18") (pinfunction "18_18") (pintype "passive"))
      (node (ref "U10") (pin "8") (pinfunction "I1_8") (pintype "bidirectional"))
    )
    (net (code "130") (name "IO82") (class "Default")
      (node (ref "CON1") (pin "88") (pinfunction "88_88") (pintype "bidirectional"))
      (node (ref "CON4") (pin "19") (pinfunction "19_19") (pintype "passive"))
      (node (ref "U10") (pin "7") (pinfunction "I2_7") (pintype "bidirectional"))
    )
    (net (code "131") (name "IO83") (class "Default")
      (node (ref "CON1") (pin "87") (pinfunction "87_87") (pintype "bidirectional"))
      (node (ref "CON4") (pin "20") (pinfunction "20_20") (pintype "passive"))
      (node (ref "U10") (pin "6") (pinfunction "I3_6") (pintype "bidirectional"))
    )
    (net (code "132") (name "IO84") (class "Default")
      (node (ref "CON1") (pin "90") (pinfunction "90_90") (pintype "bidirectional"))
      (node (ref "CON4") (pin "21") (pinfunction "21_21") (pintype "passive"))
      (node (ref "U10") (pin "5") (pinfunction "I4_5") (pintype "bidirectional"))
    )
    (net (code "133") (name "IO85") (class "Default")
      (node (ref "CON1") (pin "89") (pinfunction "89_89") (pintype "bidirectional"))
      (node (ref "CON4") (pin "22") (pinfunction "22_22") (pintype "passive"))
      (node (ref "U10") (pin "4") (pinfunction "I5_4") (pintype "bidirectional"))
    )
    (net (code "134") (name "IO86") (class "Default")
      (node (ref "CON1") (pin "92") (pinfunction "92_92") (pintype "bidirectional"))
      (node (ref "CON4") (pin "23") (pinfunction "23_23") (pintype "passive"))
      (node (ref "U10") (pin "3") (pinfunction "I6_3") (pintype "bidirectional"))
    )
    (net (code "135") (name "IO87") (class "Default")
      (node (ref "CON1") (pin "91") (pinfunction "91_91") (pintype "bidirectional"))
      (node (ref "CON4") (pin "24") (pinfunction "24_24") (pintype "passive"))
      (node (ref "U10") (pin "2") (pinfunction "I7_2") (pintype "bidirectional"))
    )
    (net (code "136") (name "IO88") (class "Default")
      (node (ref "CON1") (pin "94") (pinfunction "94_94") (pintype "bidirectional"))
      (node (ref "CON4") (pin "25") (pinfunction "25_25") (pintype "passive"))
      (node (ref "U10") (pin "23") (pinfunction "I8_23") (pintype "bidirectional"))
    )
    (net (code "137") (name "IO89") (class "Default")
      (node (ref "CON1") (pin "93") (pinfunction "93_93") (pintype "bidirectional"))
      (node (ref "CON4") (pin "26") (pinfunction "26_26") (pintype "passive"))
      (node (ref "U10") (pin "22") (pinfunction "I9_22") (pintype "bidirectional"))
    )
    (net (code "138") (name "IO90") (class "Default")
      (node (ref "CON1") (pin "96") (pinfunction "96_96") (pintype "bidirectional"))
      (node (ref "CON4") (pin "27") (pinfunction "27_27") (pintype "passive"))
      (node (ref "U10") (pin "21") (pinfunction "I10_21") (pintype "bidirectional"))
    )
    (net (code "139") (name "IO91") (class "Default")
      (node (ref "CON1") (pin "95") (pinfunction "95_95") (pintype "bidirectional"))
      (node (ref "CON4") (pin "28") (pinfunction "28_28") (pintype "passive"))
      (node (ref "U10") (pin "20") (pinfunction "I11_20") (pintype "bidirectional"))
    )
    (net (code "140") (name "IO92") (class "Default")
      (node (ref "CON1") (pin "98") (pinfunction "98_98") (pintype "bidirectional"))
      (node (ref "CON4") (pin "29") (pinfunction "29_29") (pintype "passive"))
      (node (ref "U10") (pin "19") (pinfunction "I12_19") (pintype "bidirectional"))
    )
    (net (code "141") (name "IO93") (class "Default")
      (node (ref "CON1") (pin "97") (pinfunction "97_97") (pintype "bidirectional"))
      (node (ref "CON4") (pin "30") (pinfunction "30_30") (pintype "passive"))
      (node (ref "U10") (pin "18") (pinfunction "I13_18") (pintype "bidirectional"))
    )
    (net (code "142") (name "IO94") (class "Default")
      (node (ref "CON1") (pin "100") (pinfunction "100_100") (pintype "bidirectional"))
      (node (ref "CON4") (pin "31") (pinfunction "31_31") (pintype "passive"))
      (node (ref "U10") (pin "17") (pinfunction "I14_17") (pintype "bidirectional"))
    )
    (net (code "143") (name "IO95") (class "Default")
      (node (ref "CON1") (pin "99") (pinfunction "99_99") (pintype "bidirectional"))
      (node (ref "CON4") (pin "32") (pinfunction "32_32") (pintype "passive"))
      (node (ref "U10") (pin "16") (pinfunction "I15_16") (pintype "bidirectional"))
    )
    (net (code "144") (name "IO96") (class "Default")
      (node (ref "CON1") (pin "102") (pinfunction "102_102") (pintype "bidirectional"))
      (node (ref "CON5") (pin "1") (pinfunction "1_1") (pintype "passive"))
      (node (ref "U11") (pin "9") (pinfunction "I0_9") (pintype "bidirectional"))
    )
    (net (code "145") (name "IO97") (class "Default")
      (node (ref "CON1") (pin "101") (pinfunction "101_101") (pintype "bidirectional"))
      (node (ref "CON5") (pin "2") (pinfunction "2_2") (pintype "passive"))
      (node (ref "U11") (pin "8") (pinfunction "I1_8") (pintype "bidirectional"))
    )
    (net (code "146") (name "IO98") (class "Default")
      (node (ref "CON1") (pin "104") (pinfunction "104_104") (pintype "bidirectional"))
      (node (ref "CON5") (pin "3") (pinfunction "3_3") (pintype "passive"))
      (node (ref "U11") (pin "7") (pinfunction "I2_7") (pintype "bidirectional"))
    )
    (net (code "147") (name "IO99") (class "Default")
      (node (ref "CON1") (pin "103") (pinfunction "103_103") (pintype "bidirectional"))
      (node (ref "CON5") (pin "4") (pinfunction "4_4") (pintype "passive"))
      (node (ref "U11") (pin "6") (pinfunction "I3_6") (pintype "bidirectional"))
    )
    (net (code "148") (name "IO100") (class "Default")
      (node (ref "CON1") (pin "106") (pinfunction "106_106") (pintype "bidirectional"))
      (node (ref "CON5") (pin "5") (pinfunction "5_5") (pintype "passive"))
      (node (ref "U11") (pin "5") (pinfunction "I4_5") (pintype "bidirectional"))
    )
    (net (code "149") (name "IO101") (class "Default")
      (node (ref "CON1") (pin "105") (pinfunction "105_105") (pintype "bidirectional"))
      (node (ref "CON5") (pin "6") (pinfunction "6_6") (pintype "passive"))
      (node (ref "U11") (pin "4") (pinfunction "I5_4") (pintype "bidirectional"))
    )
    (net (code "150") (name "IO102") (class "Default")
      (node (ref "CON1") (pin "108") (pinfunction "108_108") (pintype "bidirectional"))
      (node (ref "CON5") (pin "7") (pinfunction "7_7") (pintype "passive"))
      (node (ref "U11") (pin "3") (pinfunction "I6_3") (pintype "bidirectional"))
    )
    (net (code "151") (name "IO103") (class "Default")
      (node (ref "CON1") (pin "107") (pinfunction "107_107") (pintype "bidirectional"))
      (node (ref "CON5") (pin "8") (pinfunction "8_8") (pintype "passive"))
      (node (ref "U11") (pin "2") (pinfunction "I7_2") (pintype "bidirectional"))
    )
    (net (code "152") (name "IO104") (class "Default")
      (node (ref "CON1") (pin "110") (pinfunction "110_110") (pintype "bidirectional"))
      (node (ref "CON5") (pin "9") (pinfunction "9_9") (pintype "passive"))
      (node (ref "U11") (pin "23") (pinfunction "I8_23") (pintype "bidirectional"))
    )
    (net (code "153") (name "IO105") (class "Default")
      (node (ref "CON1") (pin "109") (pinfunction "109_109") (pintype "bidirectional"))
      (node (ref "CON5") (pin "10") (pinfunction "10_10") (pintype "passive"))
      (node (ref "U11") (pin "22") (pinfunction "I9_22") (pintype "bidirectional"))
    )
    (net (code "154") (name "IO106") (class "Default")
      (node (ref "CON1") (pin "112") (pinfunction "112_112") (pintype "bidirectional"))
      (node (ref "CON5") (pin "11") (pinfunction "11_11") (pintype "passive"))
      (node (ref "U11") (pin "21") (pinfunction "I10_21") (pintype "bidirectional"))
    )
    (net (code "155") (name "IO107") (class "Default")
      (node (ref "CON1") (pin "111") (pinfunction "111_111") (pintype "bidirectional"))
      (node (ref "CON5") (pin "12") (pinfunction "12_12") (pintype "passive"))
      (node (ref "U11") (pin "20") (pinfunction "I11_20") (pintype "bidirectional"))
    )
    (net (code "156") (name "IO108") (class "Default")
      (node (ref "CON1") (pin "114") (pinfunction "114_114") (pintype "bidirectional"))
      (node (ref "CON5") (pin "13") (pinfunction "13_13") (pintype "passive"))
      (node (ref "U11") (pin "19") (pinfunction "I12_19") (pintype "bidirectional"))
    )
    (net (code "157") (name "IO109") (class "Default")
      (node (ref "CON1") (pin "113") (pinfunction "113_113") (pintype "bidirectional"))
      (node (ref "CON5") (pin "14") (pinfunction "14_14") (pintype "passive"))
      (node (ref "U11") (pin "18") (pinfunction "I13_18") (pintype "bidirectional"))
    )
    (net (code "158") (name "IO110") (class "Default")
      (node (ref "CON1") (pin "116") (pinfunction "116_116") (pintype "bidirectional"))
      (node (ref "CON5") (pin "15") (pinfunction "15_15") (pintype "passive"))
      (node (ref "U11") (pin "17") (pinfunction "I14_17") (pintype "bidirectional"))
    )
    (net (code "159") (name "IO111") (class "Default")
      (node (ref "CON1") (pin "115") (pinfunction "115_115") (pintype "bidirectional"))
      (node (ref "CON5") (pin "16") (pinfunction "16_16") (pintype "passive"))
      (node (ref "U11") (pin "16") (pinfunction "I15_16") (pintype "bidirectional"))
    )
    (net (code "160") (name "IO112") (class "Default")
      (node (ref "CON1") (pin "118") (pinfunction "118_118") (pintype "bidirectional"))
      (node (ref "CON5") (pin "17") (pinfunction "17_17") (pintype "passive"))
      (node (ref "U12") (pin "9") (pinfunction "I0_9") (pintype "bidirectional"))
    )
    (net (code "161") (name "IO113") (class "Default")
      (node (ref "CON1") (pin "117") (pinfunction "117_117") (pintype "bidirectional"))
      (node (ref "CON5") (pin "18") (pinfunction "18_18") (pintype "passive"))
      (node (ref "U12") (pin "8") (pinfunction "I1_8") (pintype "bidirectional"))
    )
    (net (code "162") (name "IO114") (class "Default")
      (node (ref "CON1") (pin "120") (pinfunction "120_120") (pintype "bidirectional"))
      (node (ref "CON5") (pin "19") (pinfunction "19_19") (pintype "passive"))
      (node (ref "U12") (pin "7") (pinfunction "I2_7") (pintype "bidirectional"))
    )
    (net (code "163") (name "IO115") (class "Default")
      (node (ref "CON1") (pin "119") (pinfunction "119_119") (pintype "bidirectional"))
      (node (ref "CON5") (pin "20") (pinfunction "20_20") (pintype "passive"))
      (node (ref "U12") (pin "6") (pinfunction "I3_6") (pintype "bidirectional"))
    )
    (net (code "164") (name "IO116") (class "Default")
      (node (ref "CON1") (pin "122") (pinfunction "122_122") (pintype "bidirectional"))
      (node (ref "CON5") (pin "21") (pinfunction "21_21") (pintype "passive"))
      (node (ref "U12") (pin "5") (pinfunction "I4_5") (pintype "bidirectional"))
    )
    (net (code "165") (name "IO117") (class "Default")
      (node (ref "CON1") (pin "121") (pinfunction "121_121") (pintype "bidirectional"))
      (node (ref "CON5") (pin "22") (pinfunction "22_22") (pintype "passive"))
      (node (ref "U12") (pin "4") (pinfunction "I5_4") (pintype "bidirectional"))
    )
    (net (code "166") (name "IO118") (class "Default")
      (node (ref "CON1") (pin "124") (pinfunction "124_124") (pintype "bidirectional"))
      (node (ref "CON5") (pin "23") (pinfunction "23_23") (pintype "passive"))
      (node (ref "U12") (pin "3") (pinfunction "I6_3") (pintype "bidirectional"))
    )
    (net (code "167") (name "IO119") (class "Default")
      (node (ref "CON1") (pin "123") (pinfunction "123_123") (pintype "bidirectional"))
      (node (ref "CON5") (pin "24") (pinfunction "24_24") (pintype "passive"))
      (node (ref "U12") (pin "2") (pinfunction "I7_2") (pintype "bidirectional"))
    )
    (net (code "168") (name "IO120") (class "Default")
      (node (ref "CON1") (pin "126") (pinfunction "126_126") (pintype "bidirectional"))
      (node (ref "CON5") (pin "25") (pinfunction "25_25") (pintype "passive"))
      (node (ref "U12") (pin "23") (pinfunction "I8_23") (pintype "bidirectional"))
    )
    (net (code "169") (name "IO121") (class "Default")
      (node (ref "CON1") (pin "125") (pinfunction "125_125") (pintype "bidirectional"))
      (node (ref "CON5") (pin "26") (pinfunction "26_26") (pintype "passive"))
      (node (ref "U12") (pin "22") (pinfunction "I9_22") (pintype "bidirectional"))
    )
    (net (code "170") (name "IO122") (class "Default")
      (node (ref "CON1") (pin "128") (pinfunction "128_128") (pintype "bidirectional"))
      (node (ref "CON5") (pin "27") (pinfunction "27_27") (pintype "passive"))
      (node (ref "U12") (pin "21") (pinfunction "I10_21") (pintype "bidirectional"))
    )
    (net (code "171") (name "IO123") (class "Default")
      (node (ref "CON1") (pin "127") (pinfunction "127_127") (pintype "bidirectional"))
      (node (ref "CON5") (pin "28") (pinfunction "28_28") (pintype "passive"))
      (node (ref "U12") (pin "20") (pinfunction "I11_20") (pintype "bidirectional"))
    )
    (net (code "172") (name "IO124") (class "Default")
      (node (ref "CON1") (pin "130") (pinfunction "130_130") (pintype "bidirectional"))
      (node (ref "CON5") (pin "29") (pinfunction "29_29") (pintype "passive"))
      (node (ref "U12") (pin "19") (pinfunction "I12_19") (pintype "bidirectional"))
    )
    (net (code "173") (name "IO125") (class "Default")
      (node (ref "CON1") (pin "129") (pinfunction "129_129") (pintype "bidirectional"))
      (node (ref "CON5") (pin "30") (pinfunction "30_30") (pintype "passive"))
      (node (ref "U12") (pin "18") (pinfunction "I13_18") (pintype "bidirectional"))
    )
    (net (code "174") (name "IO126") (class "Default")
      (node (ref "CON1") (pin "132") (pinfunction "132_132") (pintype "bidirectional"))
      (node (ref "CON5") (pin "31") (pinfunction "31_31") (pintype "passive"))
      (node (ref "U12") (pin "17") (pinfunction "I14_17") (pintype "bidirectional"))
    )
    (net (code "175") (name "IO127") (class "Default")
      (node (ref "CON1") (pin "131") (pinfunction "131_131") (pintype "bidirectional"))
      (node (ref "CON5") (pin "32") (pinfunction "32_32") (pintype "passive"))
      (node (ref "U12") (pin "16") (pinfunction "I15_16") (pintype "bidirectional"))
    )
    (net (code "176") (name "LOW_RANGE_EN") (class "Default")
      (node (ref "Q4") (pin "6") (pinfunction "D1A_6") (pintype "bidirectional"))
      (node (ref "R30") (pin "2") (pinfunction "P$2_2") (pintype "passive"))
      (node (ref "R7") (pin "1") (pinfunction "P$1_1") (pintype "passive"))
    )
    (net (code "177") (name "MUX_EN") (class "Default")
      (node (ref "CON1") (pin "169") (pinfunction "169_169") (pintype "bidirectional"))
      (node (ref "CON7") (pin "10") (pinfunction "10_10") (pintype "passive"))
      (node (ref "R38") (pin "1") (pinfunction "P$1_1") (pintype "passive"))
      (node (ref "R42") (pin "1") (pinfunction "P$1_1") (pintype "passive"))
      (node (ref "R43") (pin "1") (pinfunction "P$1_1") (pintype "passive"))
      (node (ref "R44") (pin "1") (pinfunction "P$1_1") (pintype "passive"))
      (node (ref "R45") (pin "1") (pinfunction "P$1_1") (pintype "passive"))
      (node (ref "R49") (pin "1") (pinfunction "P$1_1") (pintype "passive"))
      (node (ref "R50") (pin "1") (pinfunction "P$1_1") (pintype "passive"))
      (node (ref "R51") (pin "1") (pinfunction "P$1_1") (pintype "passive"))
      (node (ref "R52") (pin "1") (pinfunction "P$1_1") (pintype "passive"))
    )
    (net (code "178") (name "Net-(C12-P$1)") (class "Default")
      (node (ref "C12") (pin "1") (pinfunction "P$1_1") (pintype "passive"))
      (node (ref "R18") (pin "1") (pinfunction "P$1_1") (pintype "passive"))
      (node (ref "R19") (pin "2") (pinfunction "P$2_2") (pintype "passive"))
      (node (ref "U3") (pin "6") (pinfunction "-INB_6") (pintype "bidirectional"))
    )
    (net (code "179") (name "Net-(C15-P$1)") (class "Default")
      (node (ref "C15") (pin "1") (pinfunction "P$1_1") (pintype "passive"))
      (node (ref "R24") (pin "1") (pinfunction "P$1_1") (pintype "passive"))
      (node (ref "R25") (pin "2") (pinfunction "P$2_2") (pintype "passive"))
      (node (ref "U2") (pin "3") (pinfunction "+INA_3") (pintype "bidirectional"))
    )
    (net (code "180") (name "Net-(Q2-G1)") (class "Default")
      (node (ref "Q2") (pin "1") (pinfunction "S1_1") (pintype "bidirectional"))
      (node (ref "Q2") (pin "2") (pinfunction "G1_2") (pintype "bidirectional"))
      (node (ref "Q2") (pin "4") (pinfunction "S2_4") (pintype "bidirectional"))
      (node (ref "Q2") (pin "5") (pinfunction "G2_5") (pintype "bidirectional"))
      (node (ref "Q3") (pin "4") (pinfunction "S2_4") (pintype "bidirectional"))
      (node (ref "Q3") (pin "5") (pinfunction "G2_5") (pintype "bidirectional"))
    )
    (net (code "181") (name "Net-(Q3-D1B)") (class "Default")
      (node (ref "Q3") (pin "7") (pinfunction "D1B_7") (pintype "bidirectional"))
      (node (ref "R20") (pin "1") (pinfunction "P$1_1") (pintype "passive"))
      (node (ref "U3") (pin "2") (pinfunction "-INA_2") (pintype "bidirectional"))
    )
    (net (code "182") (name "Net-(Q3-D2A)") (class "Default")
      (node (ref "Q3") (pin "3") (pinfunction "D2A_3") (pintype "bidirectional"))
      (node (ref "R22") (pin "1") (pinfunction "P$1_1") (pintype "passive"))
      (node (ref "U2") (pin "6") (pinfunction "-INB_6") (pintype "bidirectional"))
    )
    (net (code "183") (name "Net-(Q3-D2B)") (class "Default")
      (node (ref "Q3") (pin "8") (pinfunction "D2B_8") (pintype "bidirectional"))
      (node (ref "U2") (pin "7") (pinfunction "OUTB_7") (pintype "bidirectional"))
    )
    (net (code "184") (name "Net-(Q3-G1)") (class "Default")
      (node (ref "Q3") (pin "1") (pinfunction "S1_1") (pintype "bidirectional"))
      (node (ref "Q3") (pin "2") (pinfunction "G1_2") (pintype "bidirectional"))
      (node (ref "R17") (pin "1") (pinfunction "P$1_1") (pintype "passive"))
      (node (ref "U3") (pin "5") (pinfunction "+INB_5") (pintype "bidirectional"))
    )
    (net (code "185") (name "Net-(Q4-G1)") (class "Default")
      (node (ref "Q4") (pin "1") (pinfunction "S1_1") (pintype "bidirectional"))
      (node (ref "Q4") (pin "2") (pinfunction "G1_2") (pintype "bidirectional"))
      (node (ref "R29") (pin "2") (pinfunction "P$2_2") (pintype "passive"))
    )
    (net (code "186") (name "Net-(Q4-G2)") (class "Default")
      (node (ref "J3") (pin "2") (pinfunction "2_2") (pintype "passive"))
      (node (ref "Q4") (pin "4") (pinfunction "S2_4") (pintype "bidirectional"))
      (node (ref "Q4") (pin "5") (pinfunction "G2_5") (pintype "bidirectional"))
    )
    (net (code "187") (name "Net-(R2-P$1)") (class "Default")
      (node (ref "LED2") (pin "A") (pinfunction "A_A") (pintype "passive"))
      (node (ref "R2") (pin "1") (pinfunction "P$1_1") (pintype "passive"))
    )
    (net (code "188") (name "Net-(R3-P$1)") (class "Default")
      (node (ref "LED3") (pin "A") (pinfunction "A_A") (pintype "passive"))
      (node (ref "R3") (pin "1") (pinfunction "P$1_1") (pintype "passive"))
    )
    (net (code "189") (name "Net-(R21-P$1)") (class "Default")
      (node (ref "R21") (pin "1") (pinfunction "P$1_1") (pintype "passive"))
      (node (ref "U3") (pin "3") (pinfunction "+INA_3") (pintype "bidirectional"))
    )
    (net (code "190") (name "Net-(R23-P$1)") (class "Default")
      (node (ref "R23") (pin "1") (pinfunction "P$1_1") (pintype "passive"))
      (node (ref "U2") (pin "5") (pinfunction "+INB_5") (pintype "bidirectional"))
    )
    (net (code "191") (name "Net-(R25-P$1)") (class "Default")
      (node (ref "R25") (pin "1") (pinfunction "P$1_1") (pintype "passive"))
      (node (ref "R26") (pin "2") (pinfunction "P$2_2") (pintype "passive"))
      (node (ref "R27") (pin "2") (pinfunction "P$2_2") (pintype "passive"))
    )
    (net (code "192") (name "Net-(R33-P$1)") (class "Default")
      (node (ref "R33") (pin "1") (pinfunction "P$1_1") (pintype "passive"))
      (node (ref "U4") (pin "1") (pinfunction "1Y_1") (pintype "bidirectional"))
    )
    (net (code "193") (name "Net-(R34-P$1)") (class "Default")
      (node (ref "R34") (pin "1") (pinfunction "P$1_1") (pintype "passive"))
      (node (ref "U4") (pin "5") (pinfunction "2Y_5") (pintype "bidirectional"))
    )
    (net (code "194") (name "Net-(R35-P$1)") (class "Default")
      (node (ref "R35") (pin "1") (pinfunction "P$1_1") (pintype "passive"))
      (node (ref "U5") (pin "1") (pinfunction "1Y_1") (pintype "bidirectional"))
    )
    (net (code "195") (name "Net-(R36-P$1)") (class "Default")
      (node (ref "R36") (pin "1") (pinfunction "P$1_1") (pintype "passive"))
      (node (ref "U5") (pin "5") (pinfunction "2Y_5") (pintype "bidirectional"))
    )
    (net (code "196") (name "Net-(R38-P$2)") (class "Default")
      (node (ref "R38") (pin "2") (pinfunction "P$2_2") (pintype "passive"))
      (node (ref "U1") (pin "15") (pinfunction "\\E_15") (pintype "bidirectional"))
    )
    (net (code "197") (name "Net-(R39-P$2)") (class "Default")
      (node (ref "CON7") (pin "12") (pinfunction "12_12") (pintype "passive"))
      (node (ref "R39") (pin "2") (pinfunction "P$2_2") (pintype "passive"))
      (node (ref "R40") (pin "2") (pinfunction "P$2_2") (pintype "passive"))
      (node (ref "R41") (pin "2") (pinfunction "P$2_2") (pintype "passive"))
    )
    (net (code "198") (name "Net-(R42-P$2)") (class "Default")
      (node (ref "R42") (pin "2") (pinfunction "P$2_2") (pintype "passive"))
      (node (ref "U6") (pin "15") (pinfunction "\\E_15") (pintype "bidirectional"))
    )
    (net (code "199") (name "Net-(R43-P$2)") (class "Default")
      (node (ref "R43") (pin "2") (pinfunction "P$2_2") (pintype "passive"))
      (node (ref "U7") (pin "15") (pinfunction "\\E_15") (pintype "bidirectional"))
    )
    (net (code "200") (name "Net-(R44-P$2)") (class "Default")
      (node (ref "R44") (pin "2") (pinfunction "P$2_2") (pintype "passive"))
      (node (ref "U8") (pin "15") (pinfunction "\\E_15") (pintype "bidirectional"))
    )
    (net (code "201") (name "Net-(R45-P$2)") (class "Default")
      (node (ref "R45") (pin "2") (pinfunction "P$2_2") (pintype "passive"))
      (node (ref "U9") (pin "15") (pinfunction "\\E_15") (pintype "bidirectional"))
    )
    (net (code "202") (name "Net-(R49-P$2)") (class "Default")
      (node (ref "R49") (pin "2") (pinfunction "P$2_2") (pintype "passive"))
      (node (ref "U10") (pin "15") (pinfunction "\\E_15") (pintype "bidirectional"))
    )
    (net (code "203") (name "Net-(R50-P$2)") (class "Default")
      (node (ref "R50") (pin "2") (pinfunction "P$2_2") (pintype "passive"))
      (node (ref "U11") (pin "15") (pinfunction "\\E_15") (pintype "bidirectional"))
    )
    (net (code "204") (name "Net-(R51-P$2)") (class "Default")
      (node (ref "R51") (pin "2") (pinfunction "P$2_2") (pintype "passive"))
      (node (ref "U12") (pin "15") (pinfunction "\\E_15") (pintype "bidirectional"))
    )
    (net (code "205") (name "Net-(R52-P$2)") (class "Default")
      (node (ref "R52") (pin "2") (pinfunction "P$2_2") (pintype "passive"))
      (node (ref "U13") (pin "15") (pinfunction "\\E_15") (pintype "bidirectional"))
    )
    (net (code "206") (name "Net-(U13-I12)") (class "Default")
      (node (ref "TP8") (pin "TP") (pinfunction "TP_TP") (pintype "input"))
      (node (ref "U13") (pin "19") (pinfunction "I12_19") (pintype "bidirectional"))
    )
    (net (code "207") (name "Net-(U13-I13)") (class "Default")
      (node (ref "TP9") (pin "TP") (pinfunction "TP_TP") (pintype "input"))
      (node (ref "U13") (pin "18") (pinfunction "I13_18") (pintype "bidirectional"))
    )
    (net (code "208") (name "Net-(U13-I14)") (class "Default")
      (node (ref "TP10") (pin "TP") (pinfunction "TP_TP") (pintype "input"))
      (node (ref "U13") (pin "17") (pinfunction "I14_17") (pintype "bidirectional"))
    )
    (net (code "209") (name "Net-(U13-I15)") (class "Default")
      (node (ref "TP11") (pin "TP") (pinfunction "TP_TP") (pintype "input"))
      (node (ref "U13") (pin "16") (pinfunction "I15_16") (pintype "bidirectional"))
    )
    (net (code "210") (name "OP_VOUT") (class "Default")
      (node (ref "Q3") (pin "6") (pinfunction "D1A_6") (pintype "bidirectional"))
      (node (ref "U3") (pin "1") (pinfunction "OUTA_1") (pintype "bidirectional"))
    )
    (net (code "211") (name "VBUS") (class "Default")
      (node (ref "C13") (pin "1") (pinfunction "P$1_1") (pintype "passive"))
      (node (ref "C14") (pin "1") (pinfunction "P$1_1") (pintype "passive"))
      (node (ref "U2") (pin "8") (pinfunction "V+_8") (pintype "bidirectional"))
      (node (ref "U3") (pin "8") (pinfunction "V+_8") (pintype "bidirectional"))
    )
    (net (code "212") (name "VDDIO") (class "Default")
      (node (ref "C5") (pin "1") (pinfunction "P$1_1") (pintype "passive"))
      (node (ref "C6") (pin "1") (pinfunction "P$1_1") (pintype "passive"))
      (node (ref "CON1") (pin "1") (pinfunction "1_1") (pintype "bidirectional"))
      (node (ref "CON1") (pin "2") (pinfunction "2_2") (pintype "bidirectional"))
      (node (ref "CON1") (pin "3") (pinfunction "3_3") (pintype "bidirectional"))
      (node (ref "CON1") (pin "4") (pinfunction "4_4") (pintype "bidirectional"))
      (node (ref "CON6") (pin "12") (pinfunction "12_12") (pintype "passive"))
      (node (ref "R3") (pin "2") (pinfunction "P$2_2") (pintype "passive"))
      (node (ref "R39") (pin "1") (pinfunction "P$1_1") (pintype "passive"))
      (node (ref "TP3") (pin "TP") (pinfunction "TP_TP") (pintype "input"))
      (node (ref "U13") (pin "21") (pinfunction "I10_21") (pintype "bidirectional"))
    )
    (net (code "213") (name "VDD_BRD_PER") (class "Default")
      (node (ref "C16") (pin "2") (pinfunction "P$2_2") (pintype "passive"))
      (node (ref "C17") (pin "2") (pinfunction "P$2_2") (pintype "passive"))
      (node (ref "J3") (pin "1") (pinfunction "1_1") (pintype "passive"))
      (node (ref "Q4") (pin "7") (pinfunction "D1B_7") (pintype "bidirectional"))
      (node (ref "R20") (pin "2") (pinfunction "P$2_2") (pintype "passive"))
      (node (ref "R22") (pin "2") (pinfunction "P$2_2") (pintype "passive"))
      (node (ref "R26") (pin "1") (pinfunction "P$1_1") (pintype "passive"))
      (node (ref "R28") (pin "2") (pinfunction "P$2_2") (pintype "passive"))
      (node (ref "U4") (pin "8") (pinfunction "VCC_8") (pintype "bidirectional"))
      (node (ref "U5") (pin "8") (pinfunction "VCC_8") (pintype "bidirectional"))
    )
    (net (code "214") (name "unconnected-(CON1-Pad137)") (class "Default")
      (node (ref "CON1") (pin "137") (pinfunction "137_137") (pintype "bidirectional"))
    )
    (net (code "215") (name "unconnected-(CON1-Pad138)") (class "Default")
      (node (ref "CON1") (pin "138") (pinfunction "138_138") (pintype "bidirectional"))
    )
    (net (code "216") (name "unconnected-(CON1-Pad147)") (class "Default")
      (node (ref "CON1") (pin "147") (pinfunction "147_147") (pintype "bidirectional"))
    )
    (net (code "217") (name "unconnected-(CON1-Pad148)") (class "Default")
      (node (ref "CON1") (pin "148") (pinfunction "148_148") (pintype "bidirectional"))
    )
    (net (code "218") (name "unconnected-(CON1-Pad149)") (class "Default")
      (node (ref "CON1") (pin "149") (pinfunction "149_149") (pintype "bidirectional"))
    )
    (net (code "219") (name "unconnected-(CON1-Pad150)") (class "Default")
      (node (ref "CON1") (pin "150") (pinfunction "150_150") (pintype "bidirectional"))
    )
    (net (code "220") (name "unconnected-(CON1-Pad151)") (class "Default")
      (node (ref "CON1") (pin "151") (pinfunction "151_151") (pintype "bidirectional"))
    )
    (net (code "221") (name "unconnected-(CON1-Pad152)") (class "Default")
      (node (ref "CON1") (pin "152") (pinfunction "152_152") (pintype "bidirectional"))
    )
    (net (code "222") (name "unconnected-(CON1-Pad153)") (class "Default")
      (node (ref "CON1") (pin "153") (pinfunction "153_153") (pintype "bidirectional"))
    )
    (net (code "223") (name "unconnected-(CON1-Pad154)") (class "Default")
      (node (ref "CON1") (pin "154") (pinfunction "154_154") (pintype "bidirectional"))
    )
    (net (code "224") (name "unconnected-(CON1-Pad155)") (class "Default")
      (node (ref "CON1") (pin "155") (pinfunction "155_155") (pintype "bidirectional"))
    )
    (net (code "225") (name "unconnected-(CON1-Pad156)") (class "Default")
      (node (ref "CON1") (pin "156") (pinfunction "156_156") (pintype "bidirectional"))
    )
    (net (code "226") (name "unconnected-(CON1-Pad157)") (class "Default")
      (node (ref "CON1") (pin "157") (pinfunction "157_157") (pintype "bidirectional"))
    )
    (net (code "227") (name "unconnected-(CON1-Pad158)") (class "Default")
      (node (ref "CON1") (pin "158") (pinfunction "158_158") (pintype "bidirectional"))
    )
    (net (code "228") (name "unconnected-(CON1-Pad159)") (class "Default")
      (node (ref "CON1") (pin "159") (pinfunction "159_159") (pintype "bidirectional"))
    )
    (net (code "229") (name "unconnected-(CON1-Pad160)") (class "Default")
      (node (ref "CON1") (pin "160") (pinfunction "160_160") (pintype "bidirectional"))
    )
    (net (code "230") (name "unconnected-(CON1-Pad161)") (class "Default")
      (node (ref "CON1") (pin "161") (pinfunction "161_161") (pintype "bidirectional"))
    )
    (net (code "231") (name "unconnected-(CON1-Pad162)") (class "Default")
      (node (ref "CON1") (pin "162") (pinfunction "162_162") (pintype "bidirectional"))
    )
  )
)
